# schematic_sn74hc595n.net
KiCad netlist of a schematic drawn in Altium Designer
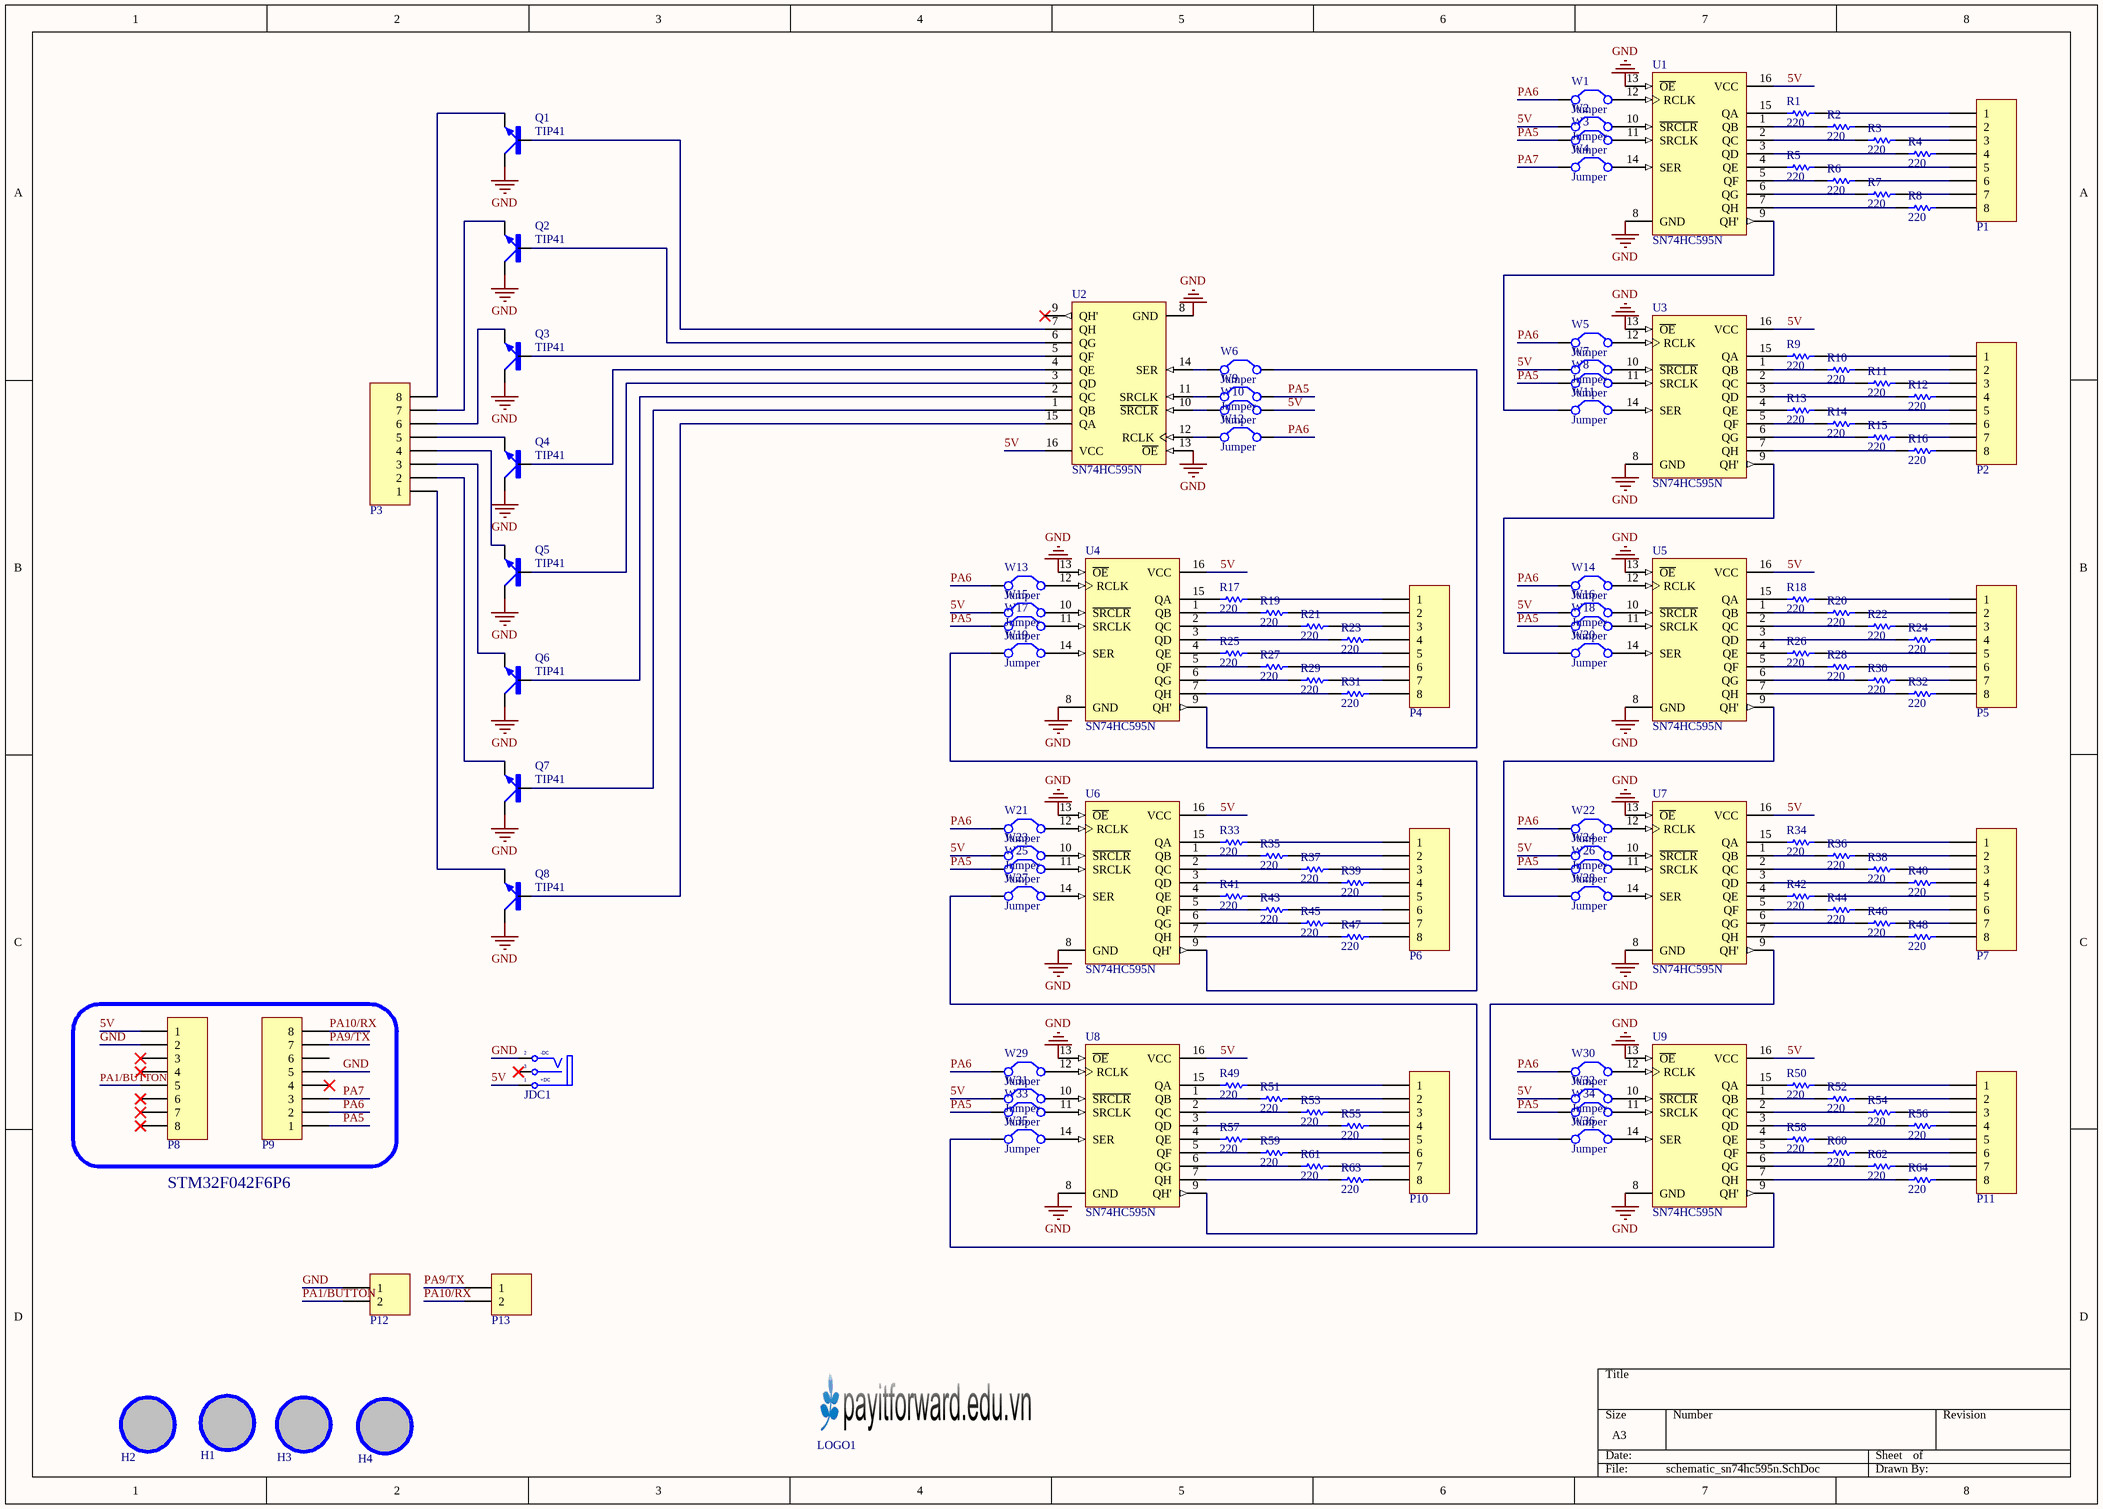
[diagram p0: schematic_sn74hc595n.SchDoc]

(export (version "E")
  (design (tool "Eeschema 10.0.6"))
  (components
    (comp (ref "H1")
      (value "Hole")
      (footprint "LO KHOAN 3MM")
      (description "Hole 3mm")
      (libsource (lib "PIF_Library") (part "Hole"))
    )
    (comp (ref "H2")
      (value "Hole")
      (footprint "LO KHOAN 3MM")
      (description "Hole 3mm")
      (libsource (lib "PIF_Library") (part "Hole"))
    )
    (comp (ref "H3")
      (value "Hole")
      (footprint "LO KHOAN 3MM")
      (description "Hole 3mm")
      (libsource (lib "PIF_Library") (part "Hole"))
    )
    (comp (ref "H4")
      (value "Hole")
      (footprint "LO KHOAN 3MM")
      (description "Hole 3mm")
      (libsource (lib "PIF_Library") (part "Hole"))
    )
    (comp (ref "JDC1")
      (value "Jack DC")
      (footprint "DC-IN")
      (description "Jack DC input")
      (libsource (lib "PIF_Library") (part "Jack DC"))
    )
    (comp (ref "LOGO1")
      (value "LOGO PIF")
      (footprint "PIF LOGO BIG SSTOP")
      (libsource (lib "PIF_Library") (part "LOGO PIF"))
    )
    (comp (ref "P1")
      (value "Header 8")
      (footprint "JP8")
      (description "Header, 8-Pin")
      (fields (field (name "PUBLISHER") "Altium Limited"))
      (libsource (lib "") (part "Header 8_1"))
    )
    (comp (ref "P2")
      (value "Header 8")
      (footprint "JP8")
      (description "Header, 8-Pin")
      (fields (field (name "PUBLISHER") "Altium Limited"))
      (libsource (lib "") (part "Header 8_1"))
    )
    (comp (ref "P3")
      (value "Header 8")
      (footprint "JP8")
      (description "Header, 8-Pin")
      (fields (field (name "PUBLISHER") "Altium Limited"))
      (libsource (lib "PIF_Library") (part "Header 8"))
    )
    (comp (ref "P4")
      (value "Header 8")
      (footprint "JP8")
      (description "Header, 8-Pin")
      (fields (field (name "PUBLISHER") "Altium Limited"))
      (libsource (lib "") (part "Header 8_1"))
    )
    (comp (ref "P5")
      (value "Header 8")
      (footprint "JP8")
      (description "Header, 8-Pin")
      (fields (field (name "PUBLISHER") "Altium Limited"))
      (libsource (lib "") (part "Header 8_1"))
    )
    (comp (ref "P6")
      (value "Header 8")
      (footprint "JP8")
      (description "Header, 8-Pin")
      (fields (field (name "PUBLISHER") "Altium Limited"))
      (libsource (lib "") (part "Header 8_1"))
    )
    (comp (ref "P7")
      (value "Header 8")
      (footprint "JP8")
      (description "Header, 8-Pin")
      (fields (field (name "PUBLISHER") "Altium Limited"))
      (libsource (lib "") (part "Header 8_1"))
    )
    (comp (ref "P8")
      (value "Header 8")
      (footprint "JP8")
      (description "Header, 8-Pin")
      (fields (field (name "PUBLISHER") "Altium Limited"))
      (libsource (lib "") (part "Header 8_1"))
    )
    (comp (ref "P9")
      (value "Header 8")
      (footprint "JP8")
      (description "Header, 8-Pin")
      (fields (field (name "PUBLISHER") "Altium Limited"))
      (libsource (lib "PIF_Library") (part "Header 8"))
    )
    (comp (ref "P10")
      (value "Header 8")
      (footprint "JP8")
      (description "Header, 8-Pin")
      (fields (field (name "PUBLISHER") "Altium Limited"))
      (libsource (lib "") (part "Header 8_1"))
    )
    (comp (ref "P11")
      (value "Header 8")
      (footprint "JP8")
      (description "Header, 8-Pin")
      (fields (field (name "PUBLISHER") "Altium Limited"))
      (libsource (lib "") (part "Header 8_1"))
    )
    (comp (ref "P12")
      (value "Header 2")
      (footprint "JP2")
      (description "Header, 2-Pin")
      (fields (field (name "PUBLISHER") "Altium Limited"))
      (libsource (lib "PIF_Library") (part "Header 2"))
    )
    (comp (ref "P13")
      (value "Header 2")
      (footprint "JP2")
      (description "Header, 2-Pin")
      (fields (field (name "PUBLISHER") "Altium Limited"))
      (libsource (lib "PIF_Library") (part "Header 2"))
    )
    (comp (ref "Q1")
      (value "TIP41")
      (footprint "TRANSISTOR-TO220AV-BCE")
      (description "Bipolar Transistors - BJT 6A 40V 65W NPN")
      (fields (field (name "MF") "ON Semiconductor"))
      (libsource (lib "TIP41") (part "TIP41"))
    )
    (comp (ref "Q2")
      (value "TIP41")
      (footprint "TRANSISTOR-TO220AV-BCE")
      (description "Bipolar Transistors - BJT 6A 40V 65W NPN")
      (fields (field (name "MF") "ON Semiconductor"))
      (libsource (lib "TIP41") (part "TIP41"))
    )
    (comp (ref "Q3")
      (value "TIP41")
      (footprint "TRANSISTOR-TO220AV-BCE")
      (description "Bipolar Transistors - BJT 6A 40V 65W NPN")
      (fields (field (name "MF") "ON Semiconductor"))
      (libsource (lib "TIP41") (part "TIP41"))
    )
    (comp (ref "Q4")
      (value "TIP41")
      (footprint "TRANSISTOR-TO220AV-BCE")
      (description "Bipolar Transistors - BJT 6A 40V 65W NPN")
      (fields (field (name "MF") "ON Semiconductor"))
      (libsource (lib "TIP41") (part "TIP41"))
    )
    (comp (ref "Q5")
      (value "TIP41")
      (footprint "TRANSISTOR-TO220AV-BCE")
      (description "Bipolar Transistors - BJT 6A 40V 65W NPN")
      (fields (field (name "MF") "ON Semiconductor"))
      (libsource (lib "TIP41") (part "TIP41"))
    )
    (comp (ref "Q6")
      (value "TIP41")
      (footprint "TRANSISTOR-TO220AV-BCE")
      (description "Bipolar Transistors - BJT 6A 40V 65W NPN")
      (fields (field (name "MF") "ON Semiconductor"))
      (libsource (lib "TIP41") (part "TIP41"))
    )
    (comp (ref "Q7")
      (value "TIP41")
      (footprint "TRANSISTOR-TO220AV-BCE")
      (description "Bipolar Transistors - BJT 6A 40V 65W NPN")
      (fields (field (name "MF") "ON Semiconductor"))
      (libsource (lib "TIP41") (part "TIP41"))
    )
    (comp (ref "Q8")
      (value "TIP41")
      (footprint "TRANSISTOR-TO220AV-BCE")
      (description "Bipolar Transistors - BJT 6A 40V 65W NPN")
      (fields (field (name "MF") "ON Semiconductor"))
      (libsource (lib "TIP41") (part "TIP41"))
    )
    (comp (ref "R1")
      (value "220")
      (footprint "RES 1/2W")
      (description "Resistor")
      (fields (field (name "Comment") "RESISTOR"))
      (libsource (lib "PIF_Library") (part "RESISTOR"))
    )
    (comp (ref "R2")
      (value "220")
      (footprint "RES 1/2W")
      (description "Resistor")
      (fields (field (name "Comment") "RESISTOR"))
      (libsource (lib "PIF_Library") (part "RESISTOR"))
    )
    (comp (ref "R3")
      (value "220")
      (footprint "RES 1/2W")
      (description "Resistor")
      (fields (field (name "Comment") "RESISTOR"))
      (libsource (lib "PIF_Library") (part "RESISTOR"))
    )
    (comp (ref "R4")
      (value "220")
      (footprint "RES 1/2W")
      (description "Resistor")
      (fields (field (name "Comment") "RESISTOR"))
      (libsource (lib "PIF_Library") (part "RESISTOR"))
    )
    (comp (ref "R5")
      (value "220")
      (footprint "RES 1/2W")
      (description "Resistor")
      (fields (field (name "Comment") "RESISTOR"))
      (libsource (lib "PIF_Library") (part "RESISTOR"))
    )
    (comp (ref "R6")
      (value "220")
      (footprint "RES 1/2W")
      (description "Resistor")
      (fields (field (name "Comment") "RESISTOR"))
      (libsource (lib "PIF_Library") (part "RESISTOR"))
    )
    (comp (ref "R7")
      (value "220")
      (footprint "RES 1/2W")
      (description "Resistor")
      (fields (field (name "Comment") "RESISTOR"))
      (libsource (lib "PIF_Library") (part "RESISTOR"))
    )
    (comp (ref "R8")
      (value "220")
      (footprint "RES 1/2W")
      (description "Resistor")
      (fields (field (name "Comment") "RESISTOR"))
      (libsource (lib "PIF_Library") (part "RESISTOR"))
    )
    (comp (ref "R9")
      (value "220")
      (footprint "RES 1/2W")
      (description "Resistor")
      (fields (field (name "Comment") "RESISTOR"))
      (libsource (lib "PIF_Library") (part "RESISTOR"))
    )
    (comp (ref "R10")
      (value "220")
      (footprint "RES 1/2W")
      (description "Resistor")
      (fields (field (name "Comment") "RESISTOR"))
      (libsource (lib "PIF_Library") (part "RESISTOR"))
    )
    (comp (ref "R11")
      (value "220")
      (footprint "RES 1/2W")
      (description "Resistor")
      (fields (field (name "Comment") "RESISTOR"))
      (libsource (lib "PIF_Library") (part "RESISTOR"))
    )
    (comp (ref "R12")
      (value "220")
      (footprint "RES 1/2W")
      (description "Resistor")
      (fields (field (name "Comment") "RESISTOR"))
      (libsource (lib "PIF_Library") (part "RESISTOR"))
    )
    (comp (ref "R13")
      (value "220")
      (footprint "RES 1/2W")
      (description "Resistor")
      (fields (field (name "Comment") "RESISTOR"))
      (libsource (lib "PIF_Library") (part "RESISTOR"))
    )
    (comp (ref "R14")
      (value "220")
      (footprint "RES 1/2W")
      (description "Resistor")
      (fields (field (name "Comment") "RESISTOR"))
      (libsource (lib "PIF_Library") (part "RESISTOR"))
    )
    (comp (ref "R15")
      (value "220")
      (footprint "RES 1/2W")
      (description "Resistor")
      (fields (field (name "Comment") "RESISTOR"))
      (libsource (lib "PIF_Library") (part "RESISTOR"))
    )
    (comp (ref "R16")
      (value "220")
      (footprint "RES 1/2W")
      (description "Resistor")
      (fields (field (name "Comment") "RESISTOR"))
      (libsource (lib "PIF_Library") (part "RESISTOR"))
    )
    (comp (ref "R17")
      (value "220")
      (footprint "RES 1/2W")
      (description "Resistor")
      (fields (field (name "Comment") "RESISTOR"))
      (libsource (lib "PIF_Library") (part "RESISTOR"))
    )
    (comp (ref "R18")
      (value "220")
      (footprint "RES 1/2W")
      (description "Resistor")
      (fields (field (name "Comment") "RESISTOR"))
      (libsource (lib "PIF_Library") (part "RESISTOR"))
    )
    (comp (ref "R19")
      (value "220")
      (footprint "RES 1/2W")
      (description "Resistor")
      (fields (field (name "Comment") "RESISTOR"))
      (libsource (lib "PIF_Library") (part "RESISTOR"))
    )
    (comp (ref "R20")
      (value "220")
      (footprint "RES 1/2W")
      (description "Resistor")
      (fields (field (name "Comment") "RESISTOR"))
      (libsource (lib "PIF_Library") (part "RESISTOR"))
    )
    (comp (ref "R21")
      (value "220")
      (footprint "RES 1/2W")
      (description "Resistor")
      (fields (field (name "Comment") "RESISTOR"))
      (libsource (lib "PIF_Library") (part "RESISTOR"))
    )
    (comp (ref "R22")
      (value "220")
      (footprint "RES 1/2W")
      (description "Resistor")
      (fields (field (name "Comment") "RESISTOR"))
      (libsource (lib "PIF_Library") (part "RESISTOR"))
    )
    (comp (ref "R23")
      (value "220")
      (footprint "RES 1/2W")
      (description "Resistor")
      (fields (field (name "Comment") "RESISTOR"))
      (libsource (lib "PIF_Library") (part "RESISTOR"))
    )
    (comp (ref "R24")
      (value "220")
      (footprint "RES 1/2W")
      (description "Resistor")
      (fields (field (name "Comment") "RESISTOR"))
      (libsource (lib "PIF_Library") (part "RESISTOR"))
    )
    (comp (ref "R25")
      (value "220")
      (footprint "RES 1/2W")
      (description "Resistor")
      (fields (field (name "Comment") "RESISTOR"))
      (libsource (lib "PIF_Library") (part "RESISTOR"))
    )
    (comp (ref "R26")
      (value "220")
      (footprint "RES 1/2W")
      (description "Resistor")
      (fields (field (name "Comment") "RESISTOR"))
      (libsource (lib "PIF_Library") (part "RESISTOR"))
    )
    (comp (ref "R27")
      (value "220")
      (footprint "RES 1/2W")
      (description "Resistor")
      (fields (field (name "Comment") "RESISTOR"))
      (libsource (lib "PIF_Library") (part "RESISTOR"))
    )
    (comp (ref "R28")
      (value "220")
      (footprint "RES 1/2W")
      (description "Resistor")
      (fields (field (name "Comment") "RESISTOR"))
      (libsource (lib "PIF_Library") (part "RESISTOR"))
    )
    (comp (ref "R29")
      (value "220")
      (footprint "RES 1/2W")
      (description "Resistor")
      (fields (field (name "Comment") "RESISTOR"))
      (libsource (lib "PIF_Library") (part "RESISTOR"))
    )
    (comp (ref "R30")
      (value "220")
      (footprint "RES 1/2W")
      (description "Resistor")
      (fields (field (name "Comment") "RESISTOR"))
      (libsource (lib "PIF_Library") (part "RESISTOR"))
    )
    (comp (ref "R31")
      (value "220")
      (footprint "RES 1/2W")
      (description "Resistor")
      (fields (field (name "Comment") "RESISTOR"))
      (libsource (lib "PIF_Library") (part "RESISTOR"))
    )
    (comp (ref "R32")
      (value "220")
      (footprint "RES 1/2W")
      (description "Resistor")
      (fields (field (name "Comment") "RESISTOR"))
      (libsource (lib "PIF_Library") (part "RESISTOR"))
    )
    (comp (ref "R33")
      (value "220")
      (footprint "RES 1/2W")
      (description "Resistor")
      (fields (field (name "Comment") "RESISTOR"))
      (libsource (lib "PIF_Library") (part "RESISTOR"))
    )
    (comp (ref "R34")
      (value "220")
      (footprint "RES 1/2W")
      (description "Resistor")
      (fields (field (name "Comment") "RESISTOR"))
      (libsource (lib "PIF_Library") (part "RESISTOR"))
    )
    (comp (ref "R35")
      (value "220")
      (footprint "RES 1/2W")
      (description "Resistor")
      (fields (field (name "Comment") "RESISTOR"))
      (libsource (lib "PIF_Library") (part "RESISTOR"))
    )
    (comp (ref "R36")
      (value "220")
      (footprint "RES 1/2W")
      (description "Resistor")
      (fields (field (name "Comment") "RESISTOR"))
      (libsource (lib "PIF_Library") (part "RESISTOR"))
    )
    (comp (ref "R37")
      (value "220")
      (footprint "RES 1/2W")
      (description "Resistor")
      (fields (field (name "Comment") "RESISTOR"))
      (libsource (lib "PIF_Library") (part "RESISTOR"))
    )
    (comp (ref "R38")
      (value "220")
      (footprint "RES 1/2W")
      (description "Resistor")
      (fields (field (name "Comment") "RESISTOR"))
      (libsource (lib "PIF_Library") (part "RESISTOR"))
    )
    (comp (ref "R39")
      (value "220")
      (footprint "RES 1/2W")
      (description "Resistor")
      (fields (field (name "Comment") "RESISTOR"))
      (libsource (lib "PIF_Library") (part "RESISTOR"))
    )
    (comp (ref "R40")
      (value "220")
      (footprint "RES 1/2W")
      (description "Resistor")
      (fields (field (name "Comment") "RESISTOR"))
      (libsource (lib "PIF_Library") (part "RESISTOR"))
    )
    (comp (ref "R41")
      (value "220")
      (footprint "RES 1/2W")
      (description "Resistor")
      (fields (field (name "Comment") "RESISTOR"))
      (libsource (lib "PIF_Library") (part "RESISTOR"))
    )
    (comp (ref "R42")
      (value "220")
      (footprint "RES 1/2W")
      (description "Resistor")
      (fields (field (name "Comment") "RESISTOR"))
      (libsource (lib "PIF_Library") (part "RESISTOR"))
    )
    (comp (ref "R43")
      (value "220")
      (footprint "RES 1/2W")
      (description "Resistor")
      (fields (field (name "Comment") "RESISTOR"))
      (libsource (lib "PIF_Library") (part "RESISTOR"))
    )
    (comp (ref "R44")
      (value "220")
      (footprint "RES 1/2W")
      (description "Resistor")
      (fields (field (name "Comment") "RESISTOR"))
      (libsource (lib "PIF_Library") (part "RESISTOR"))
    )
    (comp (ref "R45")
      (value "220")
      (footprint "RES 1/2W")
      (description "Resistor")
      (fields (field (name "Comment") "RESISTOR"))
      (libsource (lib "PIF_Library") (part "RESISTOR"))
    )
    (comp (ref "R46")
      (value "220")
      (footprint "RES 1/2W")
      (description "Resistor")
      (fields (field (name "Comment") "RESISTOR"))
      (libsource (lib "PIF_Library") (part "RESISTOR"))
    )
    (comp (ref "R47")
      (value "220")
      (footprint "RES 1/2W")
      (description "Resistor")
      (fields (field (name "Comment") "RESISTOR"))
      (libsource (lib "PIF_Library") (part "RESISTOR"))
    )
    (comp (ref "R48")
      (value "220")
      (footprint "RES 1/2W")
      (description "Resistor")
      (fields (field (name "Comment") "RESISTOR"))
      (libsource (lib "PIF_Library") (part "RESISTOR"))
    )
    (comp (ref "R49")
      (value "220")
      (footprint "RES 1/2W")
      (description "Resistor")
      (fields (field (name "Comment") "RESISTOR"))
      (libsource (lib "PIF_Library") (part "RESISTOR"))
    )
    (comp (ref "R50")
      (value "220")
      (footprint "RES 1/2W")
      (description "Resistor")
      (fields (field (name "Comment") "RESISTOR"))
      (libsource (lib "PIF_Library") (part "RESISTOR"))
    )
    (comp (ref "R51")
      (value "220")
      (footprint "RES 1/2W")
      (description "Resistor")
      (fields (field (name "Comment") "RESISTOR"))
      (libsource (lib "PIF_Library") (part "RESISTOR"))
    )
    (comp (ref "R52")
      (value "220")
      (footprint "RES 1/2W")
      (description "Resistor")
      (fields (field (name "Comment") "RESISTOR"))
      (libsource (lib "PIF_Library") (part "RESISTOR"))
    )
    (comp (ref "R53")
      (value "220")
      (footprint "RES 1/2W")
      (description "Resistor")
      (fields (field (name "Comment") "RESISTOR"))
      (libsource (lib "PIF_Library") (part "RESISTOR"))
    )
    (comp (ref "R54")
      (value "220")
      (footprint "RES 1/2W")
      (description "Resistor")
      (fields (field (name "Comment") "RESISTOR"))
      (libsource (lib "PIF_Library") (part "RESISTOR"))
    )
    (comp (ref "R55")
      (value "220")
      (footprint "RES 1/2W")
      (description "Resistor")
      (fields (field (name "Comment") "RESISTOR"))
      (libsource (lib "PIF_Library") (part "RESISTOR"))
    )
    (comp (ref "R56")
      (value "220")
      (footprint "RES 1/2W")
      (description "Resistor")
      (fields (field (name "Comment") "RESISTOR"))
      (libsource (lib "PIF_Library") (part "RESISTOR"))
    )
    (comp (ref "R57")
      (value "220")
      (footprint "RES 1/2W")
      (description "Resistor")
      (fields (field (name "Comment") "RESISTOR"))
      (libsource (lib "PIF_Library") (part "RESISTOR"))
    )
    (comp (ref "R58")
      (value "220")
      (footprint "RES 1/2W")
      (description "Resistor")
      (fields (field (name "Comment") "RESISTOR"))
      (libsource (lib "PIF_Library") (part "RESISTOR"))
    )
    (comp (ref "R59")
      (value "220")
      (footprint "RES 1/2W")
      (description "Resistor")
      (fields (field (name "Comment") "RESISTOR"))
      (libsource (lib "PIF_Library") (part "RESISTOR"))
    )
    (comp (ref "R60")
      (value "220")
      (footprint "RES 1/2W")
      (description "Resistor")
      (fields (field (name "Comment") "RESISTOR"))
      (libsource (lib "PIF_Library") (part "RESISTOR"))
    )
    (comp (ref "R61")
      (value "220")
      (footprint "RES 1/2W")
      (description "Resistor")
      (fields (field (name "Comment") "RESISTOR"))
      (libsource (lib "PIF_Library") (part "RESISTOR"))
    )
    (comp (ref "R62")
      (value "220")
      (footprint "RES 1/2W")
      (description "Resistor")
      (fields (field (name "Comment") "RESISTOR"))
      (libsource (lib "PIF_Library") (part "RESISTOR"))
    )
    (comp (ref "R63")
      (value "220")
      (footprint "RES 1/2W")
      (description "Resistor")
      (fields (field (name "Comment") "RESISTOR"))
      (libsource (lib "PIF_Library") (part "RESISTOR"))
    )
    (comp (ref "R64")
      (value "220")
      (footprint "RES 1/2W")
      (description "Resistor")
      (fields (field (name "Comment") "RESISTOR"))
      (libsource (lib "PIF_Library") (part "RESISTOR"))
    )
    (comp (ref "U1")
      (value "SN74HC595N")
      (footprint "N016")
      (description "8-Bit Shift Register with 3-State Output Registers")
      (fields (field (name "PUBLISHER") "Altium Limited"))
      (libsource (lib "TI Logic Register") (part "SN74HC595N"))
    )
    (comp (ref "U2")
      (value "SN74HC595N")
      (footprint "N016")
      (description "8-Bit Shift Register with 3-State Output Registers")
      (fields (field (name "PUBLISHER") "Altium Limited"))
      (libsource (lib "") (part "SN74HC595N_1"))
    )
    (comp (ref "U3")
      (value "SN74HC595N")
      (footprint "N016")
      (description "8-Bit Shift Register with 3-State Output Registers")
      (fields (field (name "PUBLISHER") "Altium Limited"))
      (libsource (lib "TI Logic Register") (part "SN74HC595N"))
    )
    (comp (ref "U4")
      (value "SN74HC595N")
      (footprint "N016")
      (description "8-Bit Shift Register with 3-State Output Registers")
      (fields (field (name "PUBLISHER") "Altium Limited"))
      (libsource (lib "TI Logic Register") (part "SN74HC595N"))
    )
    (comp (ref "U5")
      (value "SN74HC595N")
      (footprint "N016")
      (description "8-Bit Shift Register with 3-State Output Registers")
      (fields (field (name "PUBLISHER") "Altium Limited"))
      (libsource (lib "TI Logic Register") (part "SN74HC595N"))
    )
    (comp (ref "U6")
      (value "SN74HC595N")
      (footprint "N016")
      (description "8-Bit Shift Register with 3-State Output Registers")
      (fields (field (name "PUBLISHER") "Altium Limited"))
      (libsource (lib "TI Logic Register") (part "SN74HC595N"))
    )
    (comp (ref "U7")
      (value "SN74HC595N")
      (footprint "N016")
      (description "8-Bit Shift Register with 3-State Output Registers")
      (fields (field (name "PUBLISHER") "Altium Limited"))
      (libsource (lib "TI Logic Register") (part "SN74HC595N"))
    )
    (comp (ref "U8")
      (value "SN74HC595N")
      (footprint "N016")
      (description "8-Bit Shift Register with 3-State Output Registers")
      (fields (field (name "PUBLISHER") "Altium Limited"))
      (libsource (lib "TI Logic Register") (part "SN74HC595N"))
    )
    (comp (ref "U9")
      (value "SN74HC595N")
      (footprint "N016")
      (description "8-Bit Shift Register with 3-State Output Registers")
      (fields (field (name "PUBLISHER") "Altium Limited"))
      (libsource (lib "TI Logic Register") (part "SN74HC595N"))
    )
    (comp (ref "W1")
      (value "Jumper")
      (footprint "RAD-0.2")
      (description "Jumper Wire")
      (fields (field (name "PUBLISHER") "Altium Limited"))
      (libsource (lib "Miscellaneous Devices") (part "Jumper"))
    )
    (comp (ref "W2")
      (value "Jumper")
      (footprint "RAD-0.2")
      (description "Jumper Wire")
      (fields (field (name "PUBLISHER") "Altium Limited"))
      (libsource (lib "Miscellaneous Devices") (part "Jumper"))
    )
    (comp (ref "W3")
      (value "Jumper")
      (footprint "RAD-0.2")
      (description "Jumper Wire")
      (fields (field (name "PUBLISHER") "Altium Limited"))
      (libsource (lib "Miscellaneous Devices") (part "Jumper"))
    )
    (comp (ref "W4")
      (value "Jumper")
      (footprint "RAD-0.2")
      (description "Jumper Wire")
      (fields (field (name "PUBLISHER") "Altium Limited"))
      (libsource (lib "Miscellaneous Devices") (part "Jumper"))
    )
    (comp (ref "W5")
      (value "Jumper")
      (footprint "RAD-0.2")
      (description "Jumper Wire")
      (fields (field (name "PUBLISHER") "Altium Limited"))
      (libsource (lib "Miscellaneous Devices") (part "Jumper"))
    )
    (comp (ref "W6")
      (value "Jumper")
      (footprint "RAD-0.2")
      (description "Jumper Wire")
      (fields (field (name "PUBLISHER") "Altium Limited"))
      (libsource (lib "Miscellaneous Devices") (part "Jumper"))
    )
    (comp (ref "W7")
      (value "Jumper")
      (footprint "RAD-0.2")
      (description "Jumper Wire")
      (fields (field (name "PUBLISHER") "Altium Limited"))
      (libsource (lib "Miscellaneous Devices") (part "Jumper"))
    )
    (comp (ref "W8")
      (value "Jumper")
      (footprint "RAD-0.2")
      (description "Jumper Wire")
      (fields (field (name "PUBLISHER") "Altium Limited"))
      (libsource (lib "Miscellaneous Devices") (part "Jumper"))
    )
    (comp (ref "W9")
      (value "Jumper")
      (footprint "RAD-0.2")
      (description "Jumper Wire")
      (fields (field (name "PUBLISHER") "Altium Limited"))
      (libsource (lib "Miscellaneous Devices") (part "Jumper"))
    )
    (comp (ref "W10")
      (value "Jumper")
      (footprint "RAD-0.2")
      (description "Jumper Wire")
      (fields (field (name "PUBLISHER") "Altium Limited"))
      (libsource (lib "Miscellaneous Devices") (part "Jumper"))
    )
    (comp (ref "W11")
      (value "Jumper")
      (footprint "RAD-0.2")
      (description "Jumper Wire")
      (fields (field (name "PUBLISHER") "Altium Limited"))
      (libsource (lib "Miscellaneous Devices") (part "Jumper"))
    )
    (comp (ref "W12")
      (value "Jumper")
      (footprint "RAD-0.2")
      (description "Jumper Wire")
      (fields (field (name "PUBLISHER") "Altium Limited"))
      (libsource (lib "Miscellaneous Devices") (part "Jumper"))
    )
    (comp (ref "W13")
      (value "Jumper")
      (footprint "RAD-0.2")
      (description "Jumper Wire")
      (fields (field (name "PUBLISHER") "Altium Limited"))
      (libsource (lib "Miscellaneous Devices") (part "Jumper"))
    )
    (comp (ref "W14")
      (value "Jumper")
      (footprint "RAD-0.2")
      (description "Jumper Wire")
      (fields (field (name "PUBLISHER") "Altium Limited"))
      (libsource (lib "Miscellaneous Devices") (part "Jumper"))
    )
    (comp (ref "W15")
      (value "Jumper")
      (footprint "RAD-0.2")
      (description "Jumper Wire")
      (fields (field (name "PUBLISHER") "Altium Limited"))
      (libsource (lib "Miscellaneous Devices") (part "Jumper"))
    )
    (comp (ref "W16")
      (value "Jumper")
      (footprint "RAD-0.2")
      (description "Jumper Wire")
      (fields (field (name "PUBLISHER") "Altium Limited"))
      (libsource (lib "Miscellaneous Devices") (part "Jumper"))
    )
    (comp (ref "W17")
      (value "Jumper")
      (footprint "RAD-0.2")
      (description "Jumper Wire")
      (fields (field (name "PUBLISHER") "Altium Limited"))
      (libsource (lib "Miscellaneous Devices") (part "Jumper"))
    )
    (comp (ref "W18")
      (value "Jumper")
      (footprint "RAD-0.2")
      (description "Jumper Wire")
      (fields (field (name "PUBLISHER") "Altium Limited"))
      (libsource (lib "Miscellaneous Devices") (part "Jumper"))
    )
    (comp (ref "W19")
      (value "Jumper")
      (footprint "RAD-0.2")
      (description "Jumper Wire")
      (fields (field (name "PUBLISHER") "Altium Limited"))
      (libsource (lib "Miscellaneous Devices") (part "Jumper"))
    )
    (comp (ref "W20")
      (value "Jumper")
      (footprint "RAD-0.2")
      (description "Jumper Wire")
      (fields (field (name "PUBLISHER") "Altium Limited"))
      (libsource (lib "Miscellaneous Devices") (part "Jumper"))
    )
    (comp (ref "W21")
      (value "Jumper")
      (footprint "RAD-0.2")
      (description "Jumper Wire")
      (fields (field (name "PUBLISHER") "Altium Limited"))
      (libsource (lib "Miscellaneous Devices") (part "Jumper"))
    )
    (comp (ref "W22")
      (value "Jumper")
      (footprint "RAD-0.2")
      (description "Jumper Wire")
      (fields (field (name "PUBLISHER") "Altium Limited"))
      (libsource (lib "Miscellaneous Devices") (part "Jumper"))
    )
    (comp (ref "W23")
      (value "Jumper")
      (footprint "RAD-0.2")
      (description "Jumper Wire")
      (fields (field (name "PUBLISHER") "Altium Limited"))
      (libsource (lib "Miscellaneous Devices") (part "Jumper"))
    )
    (comp (ref "W24")
      (value "Jumper")
      (footprint "RAD-0.2")
      (description "Jumper Wire")
      (fields (field (name "PUBLISHER") "Altium Limited"))
      (libsource (lib "Miscellaneous Devices") (part "Jumper"))
    )
    (comp (ref "W25")
      (value "Jumper")
      (footprint "RAD-0.2")
      (description "Jumper Wire")
      (fields (field (name "PUBLISHER") "Altium Limited"))
      (libsource (lib "Miscellaneous Devices") (part "Jumper"))
    )
    (comp (ref "W26")
      (value "Jumper")
      (footprint "RAD-0.2")
      (description "Jumper Wire")
      (fields (field (name "PUBLISHER") "Altium Limited"))
      (libsource (lib "Miscellaneous Devices") (part "Jumper"))
    )
    (comp (ref "W27")
      (value "Jumper")
      (footprint "RAD-0.2")
      (description "Jumper Wire")
      (fields (field (name "PUBLISHER") "Altium Limited"))
      (libsource (lib "Miscellaneous Devices") (part "Jumper"))
    )
    (comp (ref "W28")
      (value "Jumper")
      (footprint "RAD-0.2")
      (description "Jumper Wire")
      (fields (field (name "PUBLISHER") "Altium Limited"))
      (libsource (lib "Miscellaneous Devices") (part "Jumper"))
    )
    (comp (ref "W29")
      (value "Jumper")
      (footprint "RAD-0.2")
      (description "Jumper Wire")
      (fields (field (name "PUBLISHER") "Altium Limited"))
      (libsource (lib "Miscellaneous Devices") (part "Jumper"))
    )
    (comp (ref "W30")
      (value "Jumper")
      (footprint "RAD-0.2")
      (description "Jumper Wire")
      (fields (field (name "PUBLISHER") "Altium Limited"))
      (libsource (lib "Miscellaneous Devices") (part "Jumper"))
    )
    (comp (ref "W31")
      (value "Jumper")
      (footprint "RAD-0.2")
      (description "Jumper Wire")
      (fields (field (name "PUBLISHER") "Altium Limited"))
      (libsource (lib "Miscellaneous Devices") (part "Jumper"))
    )
    (comp (ref "W32")
      (value "Jumper")
      (footprint "RAD-0.2")
      (description "Jumper Wire")
      (fields (field (name "PUBLISHER") "Altium Limited"))
      (libsource (lib "Miscellaneous Devices") (part "Jumper"))
    )
    (comp (ref "W33")
      (value "Jumper")
      (footprint "RAD-0.2")
      (description "Jumper Wire")
      (fields (field (name "PUBLISHER") "Altium Limited"))
      (libsource (lib "Miscellaneous Devices") (part "Jumper"))
    )
    (comp (ref "W34")
      (value "Jumper")
      (footprint "RAD-0.2")
      (description "Jumper Wire")
      (fields (field (name "PUBLISHER") "Altium Limited"))
      (libsource (lib "Miscellaneous Devices") (part "Jumper"))
    )
    (comp (ref "W35")
      (value "Jumper")
      (footprint "RAD-0.2")
      (description "Jumper Wire")
      (fields (field (name "PUBLISHER") "Altium Limited"))
      (libsource (lib "Miscellaneous Devices") (part "Jumper"))
    )
    (comp (ref "W36")
      (value "Jumper")
      (footprint "RAD-0.2")
      (description "Jumper Wire")
      (fields (field (name "PUBLISHER") "Altium Limited"))
      (libsource (lib "Miscellaneous Devices") (part "Jumper"))
    )
  )
  (nets
    (net (code "1") (name "/5V") (class "Default")
      (node (ref "JDC1") (pin "1") (pinfunction "T_1") (pintype "passive"))
      (node (ref "P8") (pin "1") (pinfunction "1_1") (pintype "passive"))
      (node (ref "U1") (pin "16") (pinfunction "VCC_16") (pintype "power_in"))
      (node (ref "U2") (pin "16") (pinfunction "VCC_16") (pintype "power_in"))
      (node (ref "U3") (pin "16") (pinfunction "VCC_16") (pintype "power_in"))
      (node (ref "U4") (pin "16") (pinfunction "VCC_16") (pintype "power_in"))
      (node (ref "U5") (pin "16") (pinfunction "VCC_16") (pintype "power_in"))
      (node (ref "U6") (pin "16") (pinfunction "VCC_16") (pintype "power_in"))
      (node (ref "U7") (pin "16") (pinfunction "VCC_16") (pintype "power_in"))
      (node (ref "U8") (pin "16") (pinfunction "VCC_16") (pintype "power_in"))
      (node (ref "U9") (pin "16") (pinfunction "VCC_16") (pintype "power_in"))
      (node (ref "W10") (pin "2") (pinfunction "C2_2") (pintype "passive"))
      (node (ref "W15") (pin "1") (pinfunction "C1_1") (pintype "passive"))
      (node (ref "W16") (pin "1") (pinfunction "C1_1") (pintype "passive"))
      (node (ref "W2") (pin "1") (pinfunction "C1_1") (pintype "passive"))
      (node (ref "W23") (pin "1") (pinfunction "C1_1") (pintype "passive"))
      (node (ref "W24") (pin "1") (pinfunction "C1_1") (pintype "passive"))
      (node (ref "W31") (pin "1") (pinfunction "C1_1") (pintype "passive"))
      (node (ref "W32") (pin "1") (pinfunction "C1_1") (pintype "passive"))
      (node (ref "W7") (pin "1") (pinfunction "C1_1") (pintype "passive"))
    )
    (net (code "2") (name "/PA1{slash}BUTTON") (class "Default")
      (node (ref "P12") (pin "2") (pinfunction "2_2") (pintype "passive"))
      (node (ref "P8") (pin "5") (pinfunction "5_5") (pintype "passive"))
    )
    (net (code "3") (name "/PA5") (class "Default")
      (node (ref "P9") (pin "1") (pinfunction "1_1") (pintype "passive"))
      (node (ref "W17") (pin "1") (pinfunction "C1_1") (pintype "passive"))
      (node (ref "W18") (pin "1") (pinfunction "C1_1") (pintype "passive"))
      (node (ref "W25") (pin "1") (pinfunction "C1_1") (pintype "passive"))
      (node (ref "W26") (pin "1") (pinfunction "C1_1") (pintype "passive"))
      (node (ref "W3") (pin "1") (pinfunction "C1_1") (pintype "passive"))
      (node (ref "W33") (pin "1") (pinfunction "C1_1") (pintype "passive"))
      (node (ref "W34") (pin "1") (pinfunction "C1_1") (pintype "passive"))
      (node (ref "W8") (pin "1") (pinfunction "C1_1") (pintype "passive"))
      (node (ref "W9") (pin "2") (pinfunction "C2_2") (pintype "passive"))
    )
    (net (code "4") (name "/PA6") (class "Default")
      (node (ref "P9") (pin "2") (pinfunction "2_2") (pintype "passive"))
      (node (ref "W1") (pin "1") (pinfunction "C1_1") (pintype "passive"))
      (node (ref "W12") (pin "2") (pinfunction "C2_2") (pintype "passive"))
      (node (ref "W13") (pin "1") (pinfunction "C1_1") (pintype "passive"))
      (node (ref "W14") (pin "1") (pinfunction "C1_1") (pintype "passive"))
      (node (ref "W21") (pin "1") (pinfunction "C1_1") (pintype "passive"))
      (node (ref "W22") (pin "1") (pinfunction "C1_1") (pintype "passive"))
      (node (ref "W29") (pin "1") (pinfunction "C1_1") (pintype "passive"))
      (node (ref "W30") (pin "1") (pinfunction "C1_1") (pintype "passive"))
      (node (ref "W5") (pin "1") (pinfunction "C1_1") (pintype "passive"))
    )
    (net (code "5") (name "/PA7") (class "Default")
      (node (ref "P9") (pin "3") (pinfunction "3_3") (pintype "passive"))
      (node (ref "W4") (pin "1") (pinfunction "C1_1") (pintype "passive"))
    )
    (net (code "6") (name "/PA9{slash}TX") (class "Default")
      (node (ref "P13") (pin "1") (pinfunction "1_1") (pintype "passive"))
      (node (ref "P9") (pin "7") (pinfunction "7_7") (pintype "passive"))
    )
    (net (code "7") (name "/PA10{slash}RX") (class "Default")
      (node (ref "P13") (pin "2") (pinfunction "2_2") (pintype "passive"))
      (node (ref "P9") (pin "8") (pinfunction "8_8") (pintype "passive"))
    )
    (net (code "8") (name "GND") (class "Default")
      (node (ref "JDC1") (pin "2") (pinfunction "TN_2") (pintype "passive"))
      (node (ref "P12") (pin "1") (pinfunction "1_1") (pintype "passive"))
      (node (ref "P8") (pin "2") (pinfunction "2_2") (pintype "passive"))
      (node (ref "P9") (pin "5") (pinfunction "5_5") (pintype "passive"))
      (node (ref "Q1") (pin "C") (pinfunction "C_C") (pintype "passive"))
      (node (ref "Q2") (pin "C") (pinfunction "C_C") (pintype "passive"))
      (node (ref "Q3") (pin "C") (pinfunction "C_C") (pintype "passive"))
      (node (ref "Q4") (pin "C") (pinfunction "C_C") (pintype "passive"))
      (node (ref "Q5") (pin "C") (pinfunction "C_C") (pintype "passive"))
      (node (ref "Q6") (pin "C") (pinfunction "C_C") (pintype "passive"))
      (node (ref "Q7") (pin "C") (pinfunction "C_C") (pintype "passive"))
      (node (ref "Q8") (pin "C") (pinfunction "C_C") (pintype "passive"))
      (node (ref "U1") (pin "13") (pinfunction "~{OE}_13") (pintype "input"))
      (node (ref "U1") (pin "8") (pinfunction "GND_8") (pintype "power_in"))
      (node (ref "U2") (pin "13") (pinfunction "~{OE}_13") (pintype "input"))
      (node (ref "U2") (pin "8") (pinfunction "GND_8") (pintype "power_in"))
      (node (ref "U3") (pin "13") (pinfunction "~{OE}_13") (pintype "input"))
      (node (ref "U3") (pin "8") (pinfunction "GND_8") (pintype "power_in"))
      (node (ref "U4") (pin "13") (pinfunction "~{OE}_13") (pintype "input"))
      (node (ref "U4") (pin "8") (pinfunction "GND_8") (pintype "power_in"))
      (node (ref "U5") (pin "13") (pinfunction "~{OE}_13") (pintype "input"))
      (node (ref "U5") (pin "8") (pinfunction "GND_8") (pintype "power_in"))
      (node (ref "U6") (pin "13") (pinfunction "~{OE}_13") (pintype "input"))
      (node (ref "U6") (pin "8") (pinfunction "GND_8") (pintype "power_in"))
      (node (ref "U7") (pin "13") (pinfunction "~{OE}_13") (pintype "input"))
      (node (ref "U7") (pin "8") (pinfunction "GND_8") (pintype "power_in"))
      (node (ref "U8") (pin "13") (pinfunction "~{OE}_13") (pintype "input"))
      (node (ref "U8") (pin "8") (pinfunction "GND_8") (pintype "power_in"))
      (node (ref "U9") (pin "13") (pinfunction "~{OE}_13") (pintype "input"))
      (node (ref "U9") (pin "8") (pinfunction "GND_8") (pintype "power_in"))
    )
    (net (code "9") (name "Net-(P1-Pad1)") (class "Default")
      (node (ref "P1") (pin "1") (pinfunction "1_1") (pintype "passive"))
      (node (ref "R1") (pin "2") (pinfunction "2_2") (pintype "passive"))
    )
    (net (code "10") (name "Net-(P1-Pad2)") (class "Default")
      (node (ref "P1") (pin "2") (pinfunction "2_2") (pintype "passive"))
      (node (ref "R2") (pin "2") (pinfunction "2_2") (pintype "passive"))
    )
    (net (code "11") (name "Net-(P1-Pad3)") (class "Default")
      (node (ref "P1") (pin "3") (pinfunction "3_3") (pintype "passive"))
      (node (ref "R3") (pin "2") (pinfunction "2_2") (pintype "passive"))
    )
    (net (code "12") (name "Net-(P1-Pad4)") (class "Default")
      (node (ref "P1") (pin "4") (pinfunction "4_4") (pintype "passive"))
      (node (ref "R4") (pin "2") (pinfunction "2_2") (pintype "passive"))
    )
    (net (code "13") (name "Net-(P1-Pad5)") (class "Default")
      (node (ref "P1") (pin "5") (pinfunction "5_5") (pintype "passive"))
      (node (ref "R5") (pin "2") (pinfunction "2_2") (pintype "passive"))
    )
    (net (code "14") (name "Net-(P1-Pad6)") (class "Default")
      (node (ref "P1") (pin "6") (pinfunction "6_6") (pintype "passive"))
      (node (ref "R6") (pin "2") (pinfunction "2_2") (pintype "passive"))
    )
    (net (code "15") (name "Net-(P1-Pad7)") (class "Default")
      (node (ref "P1") (pin "7") (pinfunction "7_7") (pintype "passive"))
      (node (ref "R7") (pin "2") (pinfunction "2_2") (pintype "passive"))
    )
    (net (code "16") (name "Net-(P1-Pad8)") (class "Default")
      (node (ref "P1") (pin "8") (pinfunction "8_8") (pintype "passive"))
      (node (ref "R8") (pin "2") (pinfunction "2_2") (pintype "passive"))
    )
    (net (code "17") (name "Net-(P2-Pad1)") (class "Default")
      (node (ref "P2") (pin "1") (pinfunction "1_1") (pintype "passive"))
      (node (ref "R9") (pin "2") (pinfunction "2_2") (pintype "passive"))
    )
    (net (code "18") (name "Net-(P2-Pad2)") (class "Default")
      (node (ref "P2") (pin "2") (pinfunction "2_2") (pintype "passive"))
      (node (ref "R10") (pin "2") (pinfunction "2_2") (pintype "passive"))
    )
    (net (code "19") (name "Net-(P2-Pad3)") (class "Default")
      (node (ref "P2") (pin "3") (pinfunction "3_3") (pintype "passive"))
      (node (ref "R11") (pin "2") (pinfunction "2_2") (pintype "passive"))
    )
    (net (code "20") (name "Net-(P2-Pad4)") (class "Default")
      (node (ref "P2") (pin "4") (pinfunction "4_4") (pintype "passive"))
      (node (ref "R12") (pin "2") (pinfunction "2_2") (pintype "passive"))
    )
    (net (code "21") (name "Net-(P2-Pad5)") (class "Default")
      (node (ref "P2") (pin "5") (pinfunction "5_5") (pintype "passive"))
      (node (ref "R13") (pin "2") (pinfunction "2_2") (pintype "passive"))
    )
    (net (code "22") (name "Net-(P2-Pad6)") (class "Default")
      (node (ref "P2") (pin "6") (pinfunction "6_6") (pintype "passive"))
      (node (ref "R14") (pin "2") (pinfunction "2_2") (pintype "passive"))
    )
    (net (code "23") (name "Net-(P2-Pad7)") (class "Default")
      (node (ref "P2") (pin "7") (pinfunction "7_7") (pintype "passive"))
      (node (ref "R15") (pin "2") (pinfunction "2_2") (pintype "passive"))
    )
    (net (code "24") (name "Net-(P2-Pad8)") (class "Default")
      (node (ref "P2") (pin "8") (pinfunction "8_8") (pintype "passive"))
      (node (ref "R16") (pin "2") (pinfunction "2_2") (pintype "passive"))
    )
    (net (code "25") (name "Net-(P3-Pad1)") (class "Default")
      (node (ref "P3") (pin "1") (pinfunction "1_1") (pintype "passive"))
      (node (ref "Q8") (pin "E") (pinfunction "E_E") (pintype "passive"))
    )
    (net (code "26") (name "Net-(P3-Pad2)") (class "Default")
      (node (ref "P3") (pin "2") (pinfunction "2_2") (pintype "passive"))
      (node (ref "Q7") (pin "E") (pinfunction "E_E") (pintype "passive"))
    )
    (net (code "27") (name "Net-(P3-Pad3)") (class "Default")
      (node (ref "P3") (pin "3") (pinfunction "3_3") (pintype "passive"))
      (node (ref "Q6") (pin "E") (pinfunction "E_E") (pintype "passive"))
    )
    (net (code "28") (name "Net-(P3-Pad4)") (class "Default")
      (node (ref "P3") (pin "4") (pinfunction "4_4") (pintype "passive"))
      (node (ref "Q5") (pin "E") (pinfunction "E_E") (pintype "passive"))
    )
    (net (code "29") (name "Net-(P3-Pad5)") (class "Default")
      (node (ref "P3") (pin "5") (pinfunction "5_5") (pintype "passive"))
      (node (ref "Q4") (pin "E") (pinfunction "E_E") (pintype "passive"))
    )
    (net (code "30") (name "Net-(P3-Pad6)") (class "Default")
      (node (ref "P3") (pin "6") (pinfunction "6_6") (pintype "passive"))
      (node (ref "Q3") (pin "E") (pinfunction "E_E") (pintype "passive"))
    )
    (net (code "31") (name "Net-(P3-Pad7)") (class "Default")
      (node (ref "P3") (pin "7") (pinfunction "7_7") (pintype "passive"))
      (node (ref "Q2") (pin "E") (pinfunction "E_E") (pintype "passive"))
    )
    (net (code "32") (name "Net-(P3-Pad8)") (class "Default")
      (node (ref "P3") (pin "8") (pinfunction "8_8") (pintype "passive"))
      (node (ref "Q1") (pin "E") (pinfunction "E_E") (pintype "passive"))
    )
    (net (code "33") (name "Net-(P4-Pad1)") (class "Default")
      (node (ref "P4") (pin "1") (pinfunction "1_1") (pintype "passive"))
      (node (ref "R17") (pin "2") (pinfunction "2_2") (pintype "passive"))
    )
    (net (code "34") (name "Net-(P4-Pad2)") (class "Default")
      (node (ref "P4") (pin "2") (pinfunction "2_2") (pintype "passive"))
      (node (ref "R19") (pin "2") (pinfunction "2_2") (pintype "passive"))
    )
    (net (code "35") (name "Net-(P4-Pad3)") (class "Default")
      (node (ref "P4") (pin "3") (pinfunction "3_3") (pintype "passive"))
      (node (ref "R21") (pin "2") (pinfunction "2_2") (pintype "passive"))
    )
    (net (code "36") (name "Net-(P4-Pad4)") (class "Default")
      (node (ref "P4") (pin "4") (pinfunction "4_4") (pintype "passive"))
      (node (ref "R23") (pin "2") (pinfunction "2_2") (pintype "passive"))
    )
    (net (code "37") (name "Net-(P4-Pad5)") (class "Default")
      (node (ref "P4") (pin "5") (pinfunction "5_5") (pintype "passive"))
      (node (ref "R25") (pin "2") (pinfunction "2_2") (pintype "passive"))
    )
    (net (code "38") (name "Net-(P4-Pad6)") (class "Default")
      (node (ref "P4") (pin "6") (pinfunction "6_6") (pintype "passive"))
      (node (ref "R27") (pin "2") (pinfunction "2_2") (pintype "passive"))
    )
    (net (code "39") (name "Net-(P4-Pad7)") (class "Default")
      (node (ref "P4") (pin "7") (pinfunction "7_7") (pintype "passive"))
      (node (ref "R29") (pin "2") (pinfunction "2_2") (pintype "passive"))
    )
    (net (code "40") (name "Net-(P4-Pad8)") (class "Default")
      (node (ref "P4") (pin "8") (pinfunction "8_8") (pintype "passive"))
      (node (ref "R31") (pin "2") (pinfunction "2_2") (pintype "passive"))
    )
    (net (code "41") (name "Net-(P5-Pad1)") (class "Default")
      (node (ref "P5") (pin "1") (pinfunction "1_1") (pintype "passive"))
      (node (ref "R18") (pin "2") (pinfunction "2_2") (pintype "passive"))
    )
    (net (code "42") (name "Net-(P5-Pad2)") (class "Default")
      (node (ref "P5") (pin "2") (pinfunction "2_2") (pintype "passive"))
      (node (ref "R20") (pin "2") (pinfunction "2_2") (pintype "passive"))
    )
    (net (code "43") (name "Net-(P5-Pad3)") (class "Default")
      (node (ref "P5") (pin "3") (pinfunction "3_3") (pintype "passive"))
      (node (ref "R22") (pin "2") (pinfunction "2_2") (pintype "passive"))
    )
    (net (code "44") (name "Net-(P5-Pad4)") (class "Default")
      (node (ref "P5") (pin "4") (pinfunction "4_4") (pintype "passive"))
      (node (ref "R24") (pin "2") (pinfunction "2_2") (pintype "passive"))
    )
    (net (code "45") (name "Net-(P5-Pad5)") (class "Default")
      (node (ref "P5") (pin "5") (pinfunction "5_5") (pintype "passive"))
      (node (ref "R26") (pin "2") (pinfunction "2_2") (pintype "passive"))
    )
    (net (code "46") (name "Net-(P5-Pad6)") (class "Default")
      (node (ref "P5") (pin "6") (pinfunction "6_6") (pintype "passive"))
      (node (ref "R28") (pin "2") (pinfunction "2_2") (pintype "passive"))
    )
    (net (code "47") (name "Net-(P5-Pad7)") (class "Default")
      (node (ref "P5") (pin "7") (pinfunction "7_7") (pintype "passive"))
      (node (ref "R30") (pin "2") (pinfunction "2_2") (pintype "passive"))
    )
    (net (code "48") (name "Net-(P5-Pad8)") (class "Default")
      (node (ref "P5") (pin "8") (pinfunction "8_8") (pintype "passive"))
      (node (ref "R32") (pin "2") (pinfunction "2_2") (pintype "passive"))
    )
    (net (code "49") (name "Net-(P6-Pad1)") (class "Default")
      (node (ref "P6") (pin "1") (pinfunction "1_1") (pintype "passive"))
      (node (ref "R33") (pin "2") (pinfunction "2_2") (pintype "passive"))
    )
    (net (code "50") (name "Net-(P6-Pad2)") (class "Default")
      (node (ref "P6") (pin "2") (pinfunction "2_2") (pintype "passive"))
      (node (ref "R35") (pin "2") (pinfunction "2_2") (pintype "passive"))
    )
    (net (code "51") (name "Net-(P6-Pad3)") (class "Default")
      (node (ref "P6") (pin "3") (pinfunction "3_3") (pintype "passive"))
      (node (ref "R37") (pin "2") (pinfunction "2_2") (pintype "passive"))
    )
    (net (code "52") (name "Net-(P6-Pad4)") (class "Default")
      (node (ref "P6") (pin "4") (pinfunction "4_4") (pintype "passive"))
      (node (ref "R39") (pin "2") (pinfunction "2_2") (pintype "passive"))
    )
    (net (code "53") (name "Net-(P6-Pad5)") (class "Default")
      (node (ref "P6") (pin "5") (pinfunction "5_5") (pintype "passive"))
      (node (ref "R41") (pin "2") (pinfunction "2_2") (pintype "passive"))
    )
    (net (code "54") (name "Net-(P6-Pad6)") (class "Default")
      (node (ref "P6") (pin "6") (pinfunction "6_6") (pintype "passive"))
      (node (ref "R43") (pin "2") (pinfunction "2_2") (pintype "passive"))
    )
    (net (code "55") (name "Net-(P6-Pad7)") (class "Default")
      (node (ref "P6") (pin "7") (pinfunction "7_7") (pintype "passive"))
      (node (ref "R45") (pin "2") (pinfunction "2_2") (pintype "passive"))
    )
    (net (code "56") (name "Net-(P6-Pad8)") (class "Default")
      (node (ref "P6") (pin "8") (pinfunction "8_8") (pintype "passive"))
      (node (ref "R47") (pin "2") (pinfunction "2_2") (pintype "passive"))
    )
    (net (code "57") (name "Net-(P7-Pad1)") (class "Default")
      (node (ref "P7") (pin "1") (pinfunction "1_1") (pintype "passive"))
      (node (ref "R34") (pin "2") (pinfunction "2_2") (pintype "passive"))
    )
    (net (code "58") (name "Net-(P7-Pad2)") (class "Default")
      (node (ref "P7") (pin "2") (pinfunction "2_2") (pintype "passive"))
      (node (ref "R36") (pin "2") (pinfunction "2_2") (pintype "passive"))
    )
    (net (code "59") (name "Net-(P7-Pad3)") (class "Default")
      (node (ref "P7") (pin "3") (pinfunction "3_3") (pintype "passive"))
      (node (ref "R38") (pin "2") (pinfunction "2_2") (pintype "passive"))
    )
    (net (code "60") (name "Net-(P7-Pad4)") (class "Default")
      (node (ref "P7") (pin "4") (pinfunction "4_4") (pintype "passive"))
      (node (ref "R40") (pin "2") (pinfunction "2_2") (pintype "passive"))
    )
    (net (code "61") (name "Net-(P7-Pad5)") (class "Default")
      (node (ref "P7") (pin "5") (pinfunction "5_5") (pintype "passive"))
      (node (ref "R42") (pin "2") (pinfunction "2_2") (pintype "passive"))
    )
    (net (code "62") (name "Net-(P7-Pad6)") (class "Default")
      (node (ref "P7") (pin "6") (pinfunction "6_6") (pintype "passive"))
      (node (ref "R44") (pin "2") (pinfunction "2_2") (pintype "passive"))
    )
    (net (code "63") (name "Net-(P7-Pad7)") (class "Default")
      (node (ref "P7") (pin "7") (pinfunction "7_7") (pintype "passive"))
      (node (ref "R46") (pin "2") (pinfunction "2_2") (pintype "passive"))
    )
    (net (code "64") (name "Net-(P7-Pad8)") (class "Default")
      (node (ref "P7") (pin "8") (pinfunction "8_8") (pintype "passive"))
      (node (ref "R48") (pin "2") (pinfunction "2_2") (pintype "passive"))
    )
    (net (code "65") (name "Net-(P10-Pad1)") (class "Default")
      (node (ref "P10") (pin "1") (pinfunction "1_1") (pintype "passive"))
      (node (ref "R49") (pin "2") (pinfunction "2_2") (pintype "passive"))
    )
    (net (code "66") (name "Net-(P10-Pad2)") (class "Default")
      (node (ref "P10") (pin "2") (pinfunction "2_2") (pintype "passive"))
      (node (ref "R51") (pin "2") (pinfunction "2_2") (pintype "passive"))
    )
    (net (code "67") (name "Net-(P10-Pad3)") (class "Default")
      (node (ref "P10") (pin "3") (pinfunction "3_3") (pintype "passive"))
      (node (ref "R53") (pin "2") (pinfunction "2_2") (pintype "passive"))
    )
    (net (code "68") (name "Net-(P10-Pad4)") (class "Default")
      (node (ref "P10") (pin "4") (pinfunction "4_4") (pintype "passive"))
      (node (ref "R55") (pin "2") (pinfunction "2_2") (pintype "passive"))
    )
    (net (code "69") (name "Net-(P10-Pad5)") (class "Default")
      (node (ref "P10") (pin "5") (pinfunction "5_5") (pintype "passive"))
      (node (ref "R57") (pin "2") (pinfunction "2_2") (pintype "passive"))
    )
    (net (code "70") (name "Net-(P10-Pad6)") (class "Default")
      (node (ref "P10") (pin "6") (pinfunction "6_6") (pintype "passive"))
      (node (ref "R59") (pin "2") (pinfunction "2_2") (pintype "passive"))
    )
    (net (code "71") (name "Net-(P10-Pad7)") (class "Default")
      (node (ref "P10") (pin "7") (pinfunction "7_7") (pintype "passive"))
      (node (ref "R61") (pin "2") (pinfunction "2_2") (pintype "passive"))
    )
    (net (code "72") (name "Net-(P10-Pad8)") (class "Default")
      (node (ref "P10") (pin "8") (pinfunction "8_8") (pintype "passive"))
      (node (ref "R63") (pin "2") (pinfunction "2_2") (pintype "passive"))
    )
    (net (code "73") (name "Net-(P11-Pad1)") (class "Default")
      (node (ref "P11") (pin "1") (pinfunction "1_1") (pintype "passive"))
      (node (ref "R50") (pin "2") (pinfunction "2_2") (pintype "passive"))
    )
    (net (code "74") (name "Net-(P11-Pad2)") (class "Default")
      (node (ref "P11") (pin "2") (pinfunction "2_2") (pintype "passive"))
      (node (ref "R52") (pin "2") (pinfunction "2_2") (pintype "passive"))
    )
    (net (code "75") (name "Net-(P11-Pad3)") (class "Default")
      (node (ref "P11") (pin "3") (pinfunction "3_3") (pintype "passive"))
      (node (ref "R54") (pin "2") (pinfunction "2_2") (pintype "passive"))
    )
    (net (code "76") (name "Net-(P11-Pad4)") (class "Default")
      (node (ref "P11") (pin "4") (pinfunction "4_4") (pintype "passive"))
      (node (ref "R56") (pin "2") (pinfunction "2_2") (pintype "passive"))
    )
    (net (code "77") (name "Net-(P11-Pad5)") (class "Default")
      (node (ref "P11") (pin "5") (pinfunction "5_5") (pintype "passive"))
      (node (ref "R58") (pin "2") (pinfunction "2_2") (pintype "passive"))
    )
    (net (code "78") (name "Net-(P11-Pad6)") (class "Default")
      (node (ref "P11") (pin "6") (pinfunction "6_6") (pintype "passive"))
      (node (ref "R60") (pin "2") (pinfunction "2_2") (pintype "passive"))
    )
    (net (code "79") (name "Net-(P11-Pad7)") (class "Default")
      (node (ref "P11") (pin "7") (pinfunction "7_7") (pintype "passive"))
      (node (ref "R62") (pin "2") (pinfunction "2_2") (pintype "passive"))
    )
    (net (code "80") (name "Net-(P11-Pad8)") (class "Default")
      (node (ref "P11") (pin "8") (pinfunction "8_8") (pintype "passive"))
      (node (ref "R64") (pin "2") (pinfunction "2_2") (pintype "passive"))
    )
    (net (code "81") (name "Net-(U1-QA)") (class "Default")
      (node (ref "R1") (pin "1") (pinfunction "1_1") (pintype "passive"))
      (node (ref "U1") (pin "15") (pinfunction "QA_15") (pintype "tri_state"))
    )
    (net (code "82") (name "Net-(U1-QB)") (class "Default")
      (node (ref "R2") (pin "1") (pinfunction "1_1") (pintype "passive"))
      (node (ref "U1") (pin "1") (pinfunction "QB_1") (pintype "tri_state"))
    )
    (net (code "83") (name "Net-(U1-QC)") (class "Default")
      (node (ref "R3") (pin "1") (pinfunction "1_1") (pintype "passive"))
      (node (ref "U1") (pin "2") (pinfunction "QC_2") (pintype "tri_state"))
    )
    (net (code "84") (name "Net-(U1-QD)") (class "Default")
      (node (ref "R4") (pin "1") (pinfunction "1_1") (pintype "passive"))
      (node (ref "U1") (pin "3") (pinfunction "QD_3") (pintype "tri_state"))
    )
    (net (code "85") (name "Net-(U1-QE)") (class "Default")
      (node (ref "R5") (pin "1") (pinfunction "1_1") (pintype "passive"))
      (node (ref "U1") (pin "4") (pinfunction "QE_4") (pintype "tri_state"))
    )
    (net (code "86") (name "Net-(U1-QF)") (class "Default")
      (node (ref "R6") (pin "1") (pinfunction "1_1") (pintype "passive"))
      (node (ref "U1") (pin "5") (pinfunction "QF_5") (pintype "tri_state"))
    )
    (net (code "87") (name "Net-(U1-QG)") (class "Default")
      (node (ref "R7") (pin "1") (pinfunction "1_1") (pintype "passive"))
      (node (ref "U1") (pin "6") (pinfunction "QG_6") (pintype "tri_state"))
    )
    (net (code "88") (name "Net-(U1-QH')") (class "Default")
      (node (ref "U1") (pin "9") (pinfunction "QH'_9") (pintype "output"))
      (node (ref "W11") (pin "1") (pinfunction "C1_1") (pintype "passive"))
    )
    (net (code "89") (name "Net-(U1-QH)") (class "Default")
      (node (ref "R8") (pin "1") (pinfunction "1_1") (pintype "passive"))
      (node (ref "U1") (pin "7") (pinfunction "QH_7") (pintype "tri_state"))
    )
    (net (code "90") (name "Net-(U1-RCLK)") (class "Default")
      (node (ref "U1") (pin "12") (pinfunction "RCLK_12") (pintype "input"))
      (node (ref "W1") (pin "2") (pinfunction "C2_2") (pintype "passive"))
    )
    (net (code "91") (name "Net-(U1-SER)") (class "Default")
      (node (ref "U1") (pin "14") (pinfunction "SER_14") (pintype "input"))
      (node (ref "W4") (pin "2") (pinfunction "C2_2") (pintype "passive"))
    )
    (net (code "92") (name "Net-(U1-SRCLK)") (class "Default")
      (node (ref "U1") (pin "11") (pinfunction "SRCLK_11") (pintype "input"))
      (node (ref "W3") (pin "2") (pinfunction "C2_2") (pintype "passive"))
    )
    (net (code "93") (name "Net-(U1-~{SRCLR})") (class "Default")
      (node (ref "U1") (pin "10") (pinfunction "~{SRCLR}_10") (pintype "input"))
      (node (ref "W2") (pin "2") (pinfunction "C2_2") (pintype "passive"))
    )
    (net (code "94") (name "Net-(U2-QA)") (class "Default")
      (node (ref "Q8") (pin "B") (pinfunction "B_B") (pintype "passive"))
      (node (ref "U2") (pin "15") (pinfunction "QA_15") (pintype "tri_state"))
    )
    (net (code "95") (name "Net-(U2-QB)") (class "Default")
      (node (ref "Q7") (pin "B") (pinfunction "B_B") (pintype "passive"))
      (node (ref "U2") (pin "1") (pinfunction "QB_1") (pintype "tri_state"))
    )
    (net (code "96") (name "Net-(U2-QC)") (class "Default")
      (node (ref "Q6") (pin "B") (pinfunction "B_B") (pintype "passive"))
      (node (ref "U2") (pin "2") (pinfunction "QC_2") (pintype "tri_state"))
    )
    (net (code "97") (name "Net-(U2-QD)") (class "Default")
      (node (ref "Q5") (pin "B") (pinfunction "B_B") (pintype "passive"))
      (node (ref "U2") (pin "3") (pinfunction "QD_3") (pintype "tri_state"))
    )
    (net (code "98") (name "Net-(U2-QE)") (class "Default")
      (node (ref "Q4") (pin "B") (pinfunction "B_B") (pintype "passive"))
      (node (ref "U2") (pin "4") (pinfunction "QE_4") (pintype "tri_state"))
    )
    (net (code "99") (name "Net-(U2-QF)") (class "Default")
      (node (ref "Q3") (pin "B") (pinfunction "B_B") (pintype "passive"))
      (node (ref "U2") (pin "5") (pinfunction "QF_5") (pintype "tri_state"))
    )
    (net (code "100") (name "Net-(U2-QG)") (class "Default")
      (node (ref "Q2") (pin "B") (pinfunction "B_B") (pintype "passive"))
      (node (ref "U2") (pin "6") (pinfunction "QG_6") (pintype "tri_state"))
    )
    (net (code "101") (name "Net-(U2-QH)") (class "Default")
      (node (ref "Q1") (pin "B") (pinfunction "B_B") (pintype "passive"))
      (node (ref "U2") (pin "7") (pinfunction "QH_7") (pintype "tri_state"))
    )
    (net (code "102") (name "Net-(U2-RCLK)") (class "Default")
      (node (ref "U2") (pin "12") (pinfunction "RCLK_12") (pintype "input"))
      (node (ref "W12") (pin "1") (pinfunction "C1_1") (pintype "passive"))
    )
    (net (code "103") (name "Net-(U2-SER)") (class "Default")
      (node (ref "U2") (pin "14") (pinfunction "SER_14") (pintype "input"))
      (node (ref "W6") (pin "1") (pinfunction "C1_1") (pintype "passive"))
    )
    (net (code "104") (name "Net-(U2-SRCLK)") (class "Default")
      (node (ref "U2") (pin "11") (pinfunction "SRCLK_11") (pintype "input"))
      (node (ref "W9") (pin "1") (pinfunction "C1_1") (pintype "passive"))
    )
    (net (code "105") (name "Net-(U2-~{SRCLR})") (class "Default")
      (node (ref "U2") (pin "10") (pinfunction "~{SRCLR}_10") (pintype "input"))
      (node (ref "W10") (pin "1") (pinfunction "C1_1") (pintype "passive"))
    )
    (net (code "106") (name "Net-(U3-QA)") (class "Default")
      (node (ref "R9") (pin "1") (pinfunction "1_1") (pintype "passive"))
      (node (ref "U3") (pin "15") (pinfunction "QA_15") (pintype "tri_state"))
    )
    (net (code "107") (name "Net-(U3-QB)") (class "Default")
      (node (ref "R10") (pin "1") (pinfunction "1_1") (pintype "passive"))
      (node (ref "U3") (pin "1") (pinfunction "QB_1") (pintype "tri_state"))
    )
    (net (code "108") (name "Net-(U3-QC)") (class "Default")
      (node (ref "R11") (pin "1") (pinfunction "1_1") (pintype "passive"))
      (node (ref "U3") (pin "2") (pinfunction "QC_2") (pintype "tri_state"))
    )
    (net (code "109") (name "Net-(U3-QD)") (class "Default")
      (node (ref "R12") (pin "1") (pinfunction "1_1") (pintype "passive"))
      (node (ref "U3") (pin "3") (pinfunction "QD_3") (pintype "tri_state"))
    )
    (net (code "110") (name "Net-(U3-QE)") (class "Default")
      (node (ref "R13") (pin "1") (pinfunction "1_1") (pintype "passive"))
      (node (ref "U3") (pin "4") (pinfunction "QE_4") (pintype "tri_state"))
    )
    (net (code "111") (name "Net-(U3-QF)") (class "Default")
      (node (ref "R14") (pin "1") (pinfunction "1_1") (pintype "passive"))
      (node (ref "U3") (pin "5") (pinfunction "QF_5") (pintype "tri_state"))
    )
    (net (code "112") (name "Net-(U3-QG)") (class "Default")
      (node (ref "R15") (pin "1") (pinfunction "1_1") (pintype "passive"))
      (node (ref "U3") (pin "6") (pinfunction "QG_6") (pintype "tri_state"))
    )
    (net (code "113") (name "Net-(U3-QH')") (class "Default")
      (node (ref "U3") (pin "9") (pinfunction "QH'_9") (pintype "output"))
      (node (ref "W20") (pin "1") (pinfunction "C1_1") (pintype "passive"))
    )
    (net (code "114") (name "Net-(U3-QH)") (class "Default")
      (node (ref "R16") (pin "1") (pinfunction "1_1") (pintype "passive"))
      (node (ref "U3") (pin "7") (pinfunction "QH_7") (pintype "tri_state"))
    )
    (net (code "115") (name "Net-(U3-RCLK)") (class "Default")
      (node (ref "U3") (pin "12") (pinfunction "RCLK_12") (pintype "input"))
      (node (ref "W5") (pin "2") (pinfunction "C2_2") (pintype "passive"))
    )
    (net (code "116") (name "Net-(U3-SER)") (class "Default")
      (node (ref "U3") (pin "14") (pinfunction "SER_14") (pintype "input"))
      (node (ref "W11") (pin "2") (pinfunction "C2_2") (pintype "passive"))
    )
    (net (code "117") (name "Net-(U3-SRCLK)") (class "Default")
      (node (ref "U3") (pin "11") (pinfunction "SRCLK_11") (pintype "input"))
      (node (ref "W8") (pin "2") (pinfunction "C2_2") (pintype "passive"))
    )
    (net (code "118") (name "Net-(U3-~{SRCLR})") (class "Default")
      (node (ref "U3") (pin "10") (pinfunction "~{SRCLR}_10") (pintype "input"))
      (node (ref "W7") (pin "2") (pinfunction "C2_2") (pintype "passive"))
    )
    (net (code "119") (name "Net-(U4-QA)") (class "Default")
      (node (ref "R17") (pin "1") (pinfunction "1_1") (pintype "passive"))
      (node (ref "U4") (pin "15") (pinfunction "QA_15") (pintype "tri_state"))
    )
    (net (code "120") (name "Net-(U4-QB)") (class "Default")
      (node (ref "R19") (pin "1") (pinfunction "1_1") (pintype "passive"))
      (node (ref "U4") (pin "1") (pinfunction "QB_1") (pintype "tri_state"))
    )
    (net (code "121") (name "Net-(U4-QC)") (class "Default")
      (node (ref "R21") (pin "1") (pinfunction "1_1") (pintype "passive"))
      (node (ref "U4") (pin "2") (pinfunction "QC_2") (pintype "tri_state"))
    )
    (net (code "122") (name "Net-(U4-QD)") (class "Default")
      (node (ref "R23") (pin "1") (pinfunction "1_1") (pintype "passive"))
      (node (ref "U4") (pin "3") (pinfunction "QD_3") (pintype "tri_state"))
    )
    (net (code "123") (name "Net-(U4-QE)") (class "Default")
      (node (ref "R25") (pin "1") (pinfunction "1_1") (pintype "passive"))
      (node (ref "U4") (pin "4") (pinfunction "QE_4") (pintype "tri_state"))
    )
    (net (code "124") (name "Net-(U4-QF)") (class "Default")
      (node (ref "R27") (pin "1") (pinfunction "1_1") (pintype "passive"))
      (node (ref "U4") (pin "5") (pinfunction "QF_5") (pintype "tri_state"))
    )
    (net (code "125") (name "Net-(U4-QG)") (class "Default")
      (node (ref "R29") (pin "1") (pinfunction "1_1") (pintype "passive"))
      (node (ref "U4") (pin "6") (pinfunction "QG_6") (pintype "tri_state"))
    )
    (net (code "126") (name "Net-(U4-QH')") (class "Default")
      (node (ref "U4") (pin "9") (pinfunction "QH'_9") (pintype "output"))
      (node (ref "W6") (pin "2") (pinfunction "C2_2") (pintype "passive"))
    )
    (net (code "127") (name "Net-(U4-QH)") (class "Default")
      (node (ref "R31") (pin "1") (pinfunction "1_1") (pintype "passive"))
      (node (ref "U4") (pin "7") (pinfunction "QH_7") (pintype "tri_state"))
    )
    (net (code "128") (name "Net-(U4-RCLK)") (class "Default")
      (node (ref "U4") (pin "12") (pinfunction "RCLK_12") (pintype "input"))
      (node (ref "W13") (pin "2") (pinfunction "C2_2") (pintype "passive"))
    )
    (net (code "129") (name "Net-(U4-SER)") (class "Default")
      (node (ref "U4") (pin "14") (pinfunction "SER_14") (pintype "input"))
      (node (ref "W19") (pin "2") (pinfunction "C2_2") (pintype "passive"))
    )
    (net (code "130") (name "Net-(U4-SRCLK)") (class "Default")
      (node (ref "U4") (pin "11") (pinfunction "SRCLK_11") (pintype "input"))
      (node (ref "W17") (pin "2") (pinfunction "C2_2") (pintype "passive"))
    )
    (net (code "131") (name "Net-(U4-~{SRCLR})") (class "Default")
      (node (ref "U4") (pin "10") (pinfunction "~{SRCLR}_10") (pintype "input"))
      (node (ref "W15") (pin "2") (pinfunction "C2_2") (pintype "passive"))
    )
    (net (code "132") (name "Net-(U5-QA)") (class "Default")
      (node (ref "R18") (pin "1") (pinfunction "1_1") (pintype "passive"))
      (node (ref "U5") (pin "15") (pinfunction "QA_15") (pintype "tri_state"))
    )
    (net (code "133") (name "Net-(U5-QB)") (class "Default")
      (node (ref "R20") (pin "1") (pinfunction "1_1") (pintype "passive"))
      (node (ref "U5") (pin "1") (pinfunction "QB_1") (pintype "tri_state"))
    )
    (net (code "134") (name "Net-(U5-QC)") (class "Default")
      (node (ref "R22") (pin "1") (pinfunction "1_1") (pintype "passive"))
      (node (ref "U5") (pin "2") (pinfunction "QC_2") (pintype "tri_state"))
    )
    (net (code "135") (name "Net-(U5-QD)") (class "Default")
      (node (ref "R24") (pin "1") (pinfunction "1_1") (pintype "passive"))
      (node (ref "U5") (pin "3") (pinfunction "QD_3") (pintype "tri_state"))
    )
    (net (code "136") (name "Net-(U5-QE)") (class "Default")
      (node (ref "R26") (pin "1") (pinfunction "1_1") (pintype "passive"))
      (node (ref "U5") (pin "4") (pinfunction "QE_4") (pintype "tri_state"))
    )
    (net (code "137") (name "Net-(U5-QF)") (class "Default")
      (node (ref "R28") (pin "1") (pinfunction "1_1") (pintype "passive"))
      (node (ref "U5") (pin "5") (pinfunction "QF_5") (pintype "tri_state"))
    )
    (net (code "138") (name "Net-(U5-QG)") (class "Default")
      (node (ref "R30") (pin "1") (pinfunction "1_1") (pintype "passive"))
      (node (ref "U5") (pin "6") (pinfunction "QG_6") (pintype "tri_state"))
    )
    (net (code "139") (name "Net-(U5-QH')") (class "Default")
      (node (ref "U5") (pin "9") (pinfunction "QH'_9") (pintype "output"))
      (node (ref "W28") (pin "1") (pinfunction "C1_1") (pintype "passive"))
    )
    (net (code "140") (name "Net-(U5-QH)") (class "Default")
      (node (ref "R32") (pin "1") (pinfunction "1_1") (pintype "passive"))
      (node (ref "U5") (pin "7") (pinfunction "QH_7") (pintype "tri_state"))
    )
    (net (code "141") (name "Net-(U5-RCLK)") (class "Default")
      (node (ref "U5") (pin "12") (pinfunction "RCLK_12") (pintype "input"))
      (node (ref "W14") (pin "2") (pinfunction "C2_2") (pintype "passive"))
    )
    (net (code "142") (name "Net-(U5-SER)") (class "Default")
      (node (ref "U5") (pin "14") (pinfunction "SER_14") (pintype "input"))
      (node (ref "W20") (pin "2") (pinfunction "C2_2") (pintype "passive"))
    )
    (net (code "143") (name "Net-(U5-SRCLK)") (class "Default")
      (node (ref "U5") (pin "11") (pinfunction "SRCLK_11") (pintype "input"))
      (node (ref "W18") (pin "2") (pinfunction "C2_2") (pintype "passive"))
    )
    (net (code "144") (name "Net-(U5-~{SRCLR})") (class "Default")
      (node (ref "U5") (pin "10") (pinfunction "~{SRCLR}_10") (pintype "input"))
      (node (ref "W16") (pin "2") (pinfunction "C2_2") (pintype "passive"))
    )
    (net (code "145") (name "Net-(U6-QA)") (class "Default")
      (node (ref "R33") (pin "1") (pinfunction "1_1") (pintype "passive"))
      (node (ref "U6") (pin "15") (pinfunction "QA_15") (pintype "tri_state"))
    )
    (net (code "146") (name "Net-(U6-QB)") (class "Default")
      (node (ref "R35") (pin "1") (pinfunction "1_1") (pintype "passive"))
      (node (ref "U6") (pin "1") (pinfunction "QB_1") (pintype "tri_state"))
    )
    (net (code "147") (name "Net-(U6-QC)") (class "Default")
      (node (ref "R37") (pin "1") (pinfunction "1_1") (pintype "passive"))
      (node (ref "U6") (pin "2") (pinfunction "QC_2") (pintype "tri_state"))
    )
    (net (code "148") (name "Net-(U6-QD)") (class "Default")
      (node (ref "R39") (pin "1") (pinfunction "1_1") (pintype "passive"))
      (node (ref "U6") (pin "3") (pinfunction "QD_3") (pintype "tri_state"))
    )
    (net (code "149") (name "Net-(U6-QE)") (class "Default")
      (node (ref "R41") (pin "1") (pinfunction "1_1") (pintype "passive"))
      (node (ref "U6") (pin "4") (pinfunction "QE_4") (pintype "tri_state"))
    )
    (net (code "150") (name "Net-(U6-QF)") (class "Default")
      (node (ref "R43") (pin "1") (pinfunction "1_1") (pintype "passive"))
      (node (ref "U6") (pin "5") (pinfunction "QF_5") (pintype "tri_state"))
    )
    (net (code "151") (name "Net-(U6-QG)") (class "Default")
      (node (ref "R45") (pin "1") (pinfunction "1_1") (pintype "passive"))
      (node (ref "U6") (pin "6") (pinfunction "QG_6") (pintype "tri_state"))
    )
    (net (code "152") (name "Net-(U6-QH')") (class "Default")
      (node (ref "U6") (pin "9") (pinfunction "QH'_9") (pintype "output"))
      (node (ref "W19") (pin "1") (pinfunction "C1_1") (pintype "passive"))
    )
    (net (code "153") (name "Net-(U6-QH)") (class "Default")
      (node (ref "R47") (pin "1") (pinfunction "1_1") (pintype "passive"))
      (node (ref "U6") (pin "7") (pinfunction "QH_7") (pintype "tri_state"))
    )
    (net (code "154") (name "Net-(U6-RCLK)") (class "Default")
      (node (ref "U6") (pin "12") (pinfunction "RCLK_12") (pintype "input"))
      (node (ref "W21") (pin "2") (pinfunction "C2_2") (pintype "passive"))
    )
    (net (code "155") (name "Net-(U6-SER)") (class "Default")
      (node (ref "U6") (pin "14") (pinfunction "SER_14") (pintype "input"))
      (node (ref "W27") (pin "2") (pinfunction "C2_2") (pintype "passive"))
    )
    (net (code "156") (name "Net-(U6-SRCLK)") (class "Default")
      (node (ref "U6") (pin "11") (pinfunction "SRCLK_11") (pintype "input"))
      (node (ref "W25") (pin "2") (pinfunction "C2_2") (pintype "passive"))
    )
    (net (code "157") (name "Net-(U6-~{SRCLR})") (class "Default")
      (node (ref "U6") (pin "10") (pinfunction "~{SRCLR}_10") (pintype "input"))
      (node (ref "W23") (pin "2") (pinfunction "C2_2") (pintype "passive"))
    )
    (net (code "158") (name "Net-(U7-QA)") (class "Default")
      (node (ref "R34") (pin "1") (pinfunction "1_1") (pintype "passive"))
      (node (ref "U7") (pin "15") (pinfunction "QA_15") (pintype "tri_state"))
    )
    (net (code "159") (name "Net-(U7-QB)") (class "Default")
      (node (ref "R36") (pin "1") (pinfunction "1_1") (pintype "passive"))
      (node (ref "U7") (pin "1") (pinfunction "QB_1") (pintype "tri_state"))
    )
    (net (code "160") (name "Net-(U7-QC)") (class "Default")
      (node (ref "R38") (pin "1") (pinfunction "1_1") (pintype "passive"))
      (node (ref "U7") (pin "2") (pinfunction "QC_2") (pintype "tri_state"))
    )
    (net (code "161") (name "Net-(U7-QD)") (class "Default")
      (node (ref "R40") (pin "1") (pinfunction "1_1") (pintype "passive"))
      (node (ref "U7") (pin "3") (pinfunction "QD_3") (pintype "tri_state"))
    )
    (net (code "162") (name "Net-(U7-QE)") (class "Default")
      (node (ref "R42") (pin "1") (pinfunction "1_1") (pintype "passive"))
      (node (ref "U7") (pin "4") (pinfunction "QE_4") (pintype "tri_state"))
    )
    (net (code "163") (name "Net-(U7-QF)") (class "Default")
      (node (ref "R44") (pin "1") (pinfunction "1_1") (pintype "passive"))
      (node (ref "U7") (pin "5") (pinfunction "QF_5") (pintype "tri_state"))
    )
    (net (code "164") (name "Net-(U7-QG)") (class "Default")
      (node (ref "R46") (pin "1") (pinfunction "1_1") (pintype "passive"))
      (node (ref "U7") (pin "6") (pinfunction "QG_6") (pintype "tri_state"))
    )
    (net (code "165") (name "Net-(U7-QH')") (class "Default")
      (node (ref "U7") (pin "9") (pinfunction "QH'_9") (pintype "output"))
      (node (ref "W36") (pin "1") (pinfunction "C1_1") (pintype "passive"))
    )
    (net (code "166") (name "Net-(U7-QH)") (class "Default")
      (node (ref "R48") (pin "1") (pinfunction "1_1") (pintype "passive"))
      (node (ref "U7") (pin "7") (pinfunction "QH_7") (pintype "tri_state"))
    )
    (net (code "167") (name "Net-(U7-RCLK)") (class "Default")
      (node (ref "U7") (pin "12") (pinfunction "RCLK_12") (pintype "input"))
      (node (ref "W22") (pin "2") (pinfunction "C2_2") (pintype "passive"))
    )
    (net (code "168") (name "Net-(U7-SER)") (class "Default")
      (node (ref "U7") (pin "14") (pinfunction "SER_14") (pintype "input"))
      (node (ref "W28") (pin "2") (pinfunction "C2_2") (pintype "passive"))
    )
    (net (code "169") (name "Net-(U7-SRCLK)") (class "Default")
      (node (ref "U7") (pin "11") (pinfunction "SRCLK_11") (pintype "input"))
      (node (ref "W26") (pin "2") (pinfunction "C2_2") (pintype "passive"))
    )
    (net (code "170") (name "Net-(U7-~{SRCLR})") (class "Default")
      (node (ref "U7") (pin "10") (pinfunction "~{SRCLR}_10") (pintype "input"))
      (node (ref "W24") (pin "2") (pinfunction "C2_2") (pintype "passive"))
    )
    (net (code "171") (name "Net-(U8-QA)") (class "Default")
      (node (ref "R49") (pin "1") (pinfunction "1_1") (pintype "passive"))
      (node (ref "U8") (pin "15") (pinfunction "QA_15") (pintype "tri_state"))
    )
    (net (code "172") (name "Net-(U8-QB)") (class "Default")
      (node (ref "R51") (pin "1") (pinfunction "1_1") (pintype "passive"))
      (node (ref "U8") (pin "1") (pinfunction "QB_1") (pintype "tri_state"))
    )
    (net (code "173") (name "Net-(U8-QC)") (class "Default")
      (node (ref "R53") (pin "1") (pinfunction "1_1") (pintype "passive"))
      (node (ref "U8") (pin "2") (pinfunction "QC_2") (pintype "tri_state"))
    )
    (net (code "174") (name "Net-(U8-QD)") (class "Default")
      (node (ref "R55") (pin "1") (pinfunction "1_1") (pintype "passive"))
      (node (ref "U8") (pin "3") (pinfunction "QD_3") (pintype "tri_state"))
    )
    (net (code "175") (name "Net-(U8-QE)") (class "Default")
      (node (ref "R57") (pin "1") (pinfunction "1_1") (pintype "passive"))
      (node (ref "U8") (pin "4") (pinfunction "QE_4") (pintype "tri_state"))
    )
    (net (code "176") (name "Net-(U8-QF)") (class "Default")
      (node (ref "R59") (pin "1") (pinfunction "1_1") (pintype "passive"))
      (node (ref "U8") (pin "5") (pinfunction "QF_5") (pintype "tri_state"))
    )
    (net (code "177") (name "Net-(U8-QG)") (class "Default")
      (node (ref "R61") (pin "1") (pinfunction "1_1") (pintype "passive"))
      (node (ref "U8") (pin "6") (pinfunction "QG_6") (pintype "tri_state"))
    )
    (net (code "178") (name "Net-(U8-QH')") (class "Default")
      (node (ref "U8") (pin "9") (pinfunction "QH'_9") (pintype "output"))
      (node (ref "W27") (pin "1") (pinfunction "C1_1") (pintype "passive"))
    )
    (net (code "179") (name "Net-(U8-QH)") (class "Default")
      (node (ref "R63") (pin "1") (pinfunction "1_1") (pintype "passive"))
      (node (ref "U8") (pin "7") (pinfunction "QH_7") (pintype "tri_state"))
    )
    (net (code "180") (name "Net-(U8-RCLK)") (class "Default")
      (node (ref "U8") (pin "12") (pinfunction "RCLK_12") (pintype "input"))
      (node (ref "W29") (pin "2") (pinfunction "C2_2") (pintype "passive"))
    )
    (net (code "181") (name "Net-(U8-SER)") (class "Default")
      (node (ref "U8") (pin "14") (pinfunction "SER_14") (pintype "input"))
      (node (ref "W35") (pin "2") (pinfunction "C2_2") (pintype "passive"))
    )
    (net (code "182") (name "Net-(U8-SRCLK)") (class "Default")
      (node (ref "U8") (pin "11") (pinfunction "SRCLK_11") (pintype "input"))
      (node (ref "W33") (pin "2") (pinfunction "C2_2") (pintype "passive"))
    )
    (net (code "183") (name "Net-(U8-~{SRCLR})") (class "Default")
      (node (ref "U8") (pin "10") (pinfunction "~{SRCLR}_10") (pintype "input"))
      (node (ref "W31") (pin "2") (pinfunction "C2_2") (pintype "passive"))
    )
    (net (code "184") (name "Net-(U9-QA)") (class "Default")
      (node (ref "R50") (pin "1") (pinfunction "1_1") (pintype "passive"))
      (node (ref "U9") (pin "15") (pinfunction "QA_15") (pintype "tri_state"))
    )
    (net (code "185") (name "Net-(U9-QB)") (class "Default")
      (node (ref "R52") (pin "1") (pinfunction "1_1") (pintype "passive"))
      (node (ref "U9") (pin "1") (pinfunction "QB_1") (pintype "tri_state"))
    )
    (net (code "186") (name "Net-(U9-QC)") (class "Default")
      (node (ref "R54") (pin "1") (pinfunction "1_1") (pintype "passive"))
      (node (ref "U9") (pin "2") (pinfunction "QC_2") (pintype "tri_state"))
    )
    (net (code "187") (name "Net-(U9-QD)") (class "Default")
      (node (ref "R56") (pin "1") (pinfunction "1_1") (pintype "passive"))
      (node (ref "U9") (pin "3") (pinfunction "QD_3") (pintype "tri_state"))
    )
    (net (code "188") (name "Net-(U9-QE)") (class "Default")
      (node (ref "R58") (pin "1") (pinfunction "1_1") (pintype "passive"))
      (node (ref "U9") (pin "4") (pinfunction "QE_4") (pintype "tri_state"))
    )
    (net (code "189") (name "Net-(U9-QF)") (class "Default")
      (node (ref "R60") (pin "1") (pinfunction "1_1") (pintype "passive"))
      (node (ref "U9") (pin "5") (pinfunction "QF_5") (pintype "tri_state"))
    )
    (net (code "190") (name "Net-(U9-QG)") (class "Default")
      (node (ref "R62") (pin "1") (pinfunction "1_1") (pintype "passive"))
      (node (ref "U9") (pin "6") (pinfunction "QG_6") (pintype "tri_state"))
    )
    (net (code "191") (name "Net-(U9-QH')") (class "Default")
      (node (ref "U9") (pin "9") (pinfunction "QH'_9") (pintype "output"))
      (node (ref "W35") (pin "1") (pinfunction "C1_1") (pintype "passive"))
    )
    (net (code "192") (name "Net-(U9-QH)") (class "Default")
      (node (ref "R64") (pin "1") (pinfunction "1_1") (pintype "passive"))
      (node (ref "U9") (pin "7") (pinfunction "QH_7") (pintype "tri_state"))
    )
    (net (code "193") (name "Net-(U9-RCLK)") (class "Default")
      (node (ref "U9") (pin "12") (pinfunction "RCLK_12") (pintype "input"))
      (node (ref "W30") (pin "2") (pinfunction "C2_2") (pintype "passive"))
    )
    (net (code "194") (name "Net-(U9-SER)") (class "Default")
      (node (ref "U9") (pin "14") (pinfunction "SER_14") (pintype "input"))
      (node (ref "W36") (pin "2") (pinfunction "C2_2") (pintype "passive"))
    )
    (net (code "195") (name "Net-(U9-SRCLK)") (class "Default")
      (node (ref "U9") (pin "11") (pinfunction "SRCLK_11") (pintype "input"))
      (node (ref "W34") (pin "2") (pinfunction "C2_2") (pintype "passive"))
    )
    (net (code "196") (name "Net-(U9-~{SRCLR})") (class "Default")
      (node (ref "U9") (pin "10") (pinfunction "~{SRCLR}_10") (pintype "input"))
      (node (ref "W32") (pin "2") (pinfunction "C2_2") (pintype "passive"))
    )
    (net (code "197") (name "unconnected-(H1-Pad1)") (class "Default")
      (node (ref "H1") (pin "1") (pinfunction "1_1") (pintype "passive"))
    )
    (net (code "198") (name "unconnected-(H2-Pad1)") (class "Default")
      (node (ref "H2") (pin "1") (pinfunction "1_1") (pintype "passive"))
    )
    (net (code "199") (name "unconnected-(H3-Pad1)") (class "Default")
      (node (ref "H3") (pin "1") (pinfunction "1_1") (pintype "passive"))
    )
    (net (code "200") (name "unconnected-(H4-Pad1)") (class "Default")
      (node (ref "H4") (pin "1") (pinfunction "1_1") (pintype "passive"))
    )
    (net (code "201") (name "unconnected-(JDC1-S-Pad3)") (class "Default")
      (node (ref "JDC1") (pin "3") (pinfunction "S_3") (pintype "power_in+no_connect"))
    )
    (net (code "202") (name "unconnected-(P8-Pad3)") (class "Default")
      (node (ref "P8") (pin "3") (pinfunction "3_3") (pintype "passive+no_connect"))
    )
    (net (code "203") (name "unconnected-(P8-Pad4)") (class "Default")
      (node (ref "P8") (pin "4") (pinfunction "4_4") (pintype "passive+no_connect"))
    )
    (net (code "204") (name "unconnected-(P8-Pad6)") (class "Default")
      (node (ref "P8") (pin "6") (pinfunction "6_6") (pintype "passive+no_connect"))
    )
    (net (code "205") (name "unconnected-(P8-Pad7)") (class "Default")
      (node (ref "P8") (pin "7") (pinfunction "7_7") (pintype "passive+no_connect"))
    )
    (net (code "206") (name "unconnected-(P8-Pad8)") (class "Default")
      (node (ref "P8") (pin "8") (pinfunction "8_8") (pintype "passive+no_connect"))
    )
    (net (code "207") (name "unconnected-(P9-Pad4)") (class "Default")
      (node (ref "P9") (pin "4") (pinfunction "4_4") (pintype "passive+no_connect"))
    )
    (net (code "208") (name "unconnected-(P9-Pad6)") (class "Default")
      (node (ref "P9") (pin "6") (pinfunction "6_6") (pintype "passive"))
    )
    (net (code "209") (name "unconnected-(U2-QH'-Pad9)") (class "Default")
      (node (ref "U2") (pin "9") (pinfunction "QH'_9") (pintype "output+no_connect"))
    )
  )
)
